# keyboardPCB2.net
KiCad netlist of a schematic drawn in EAGLE
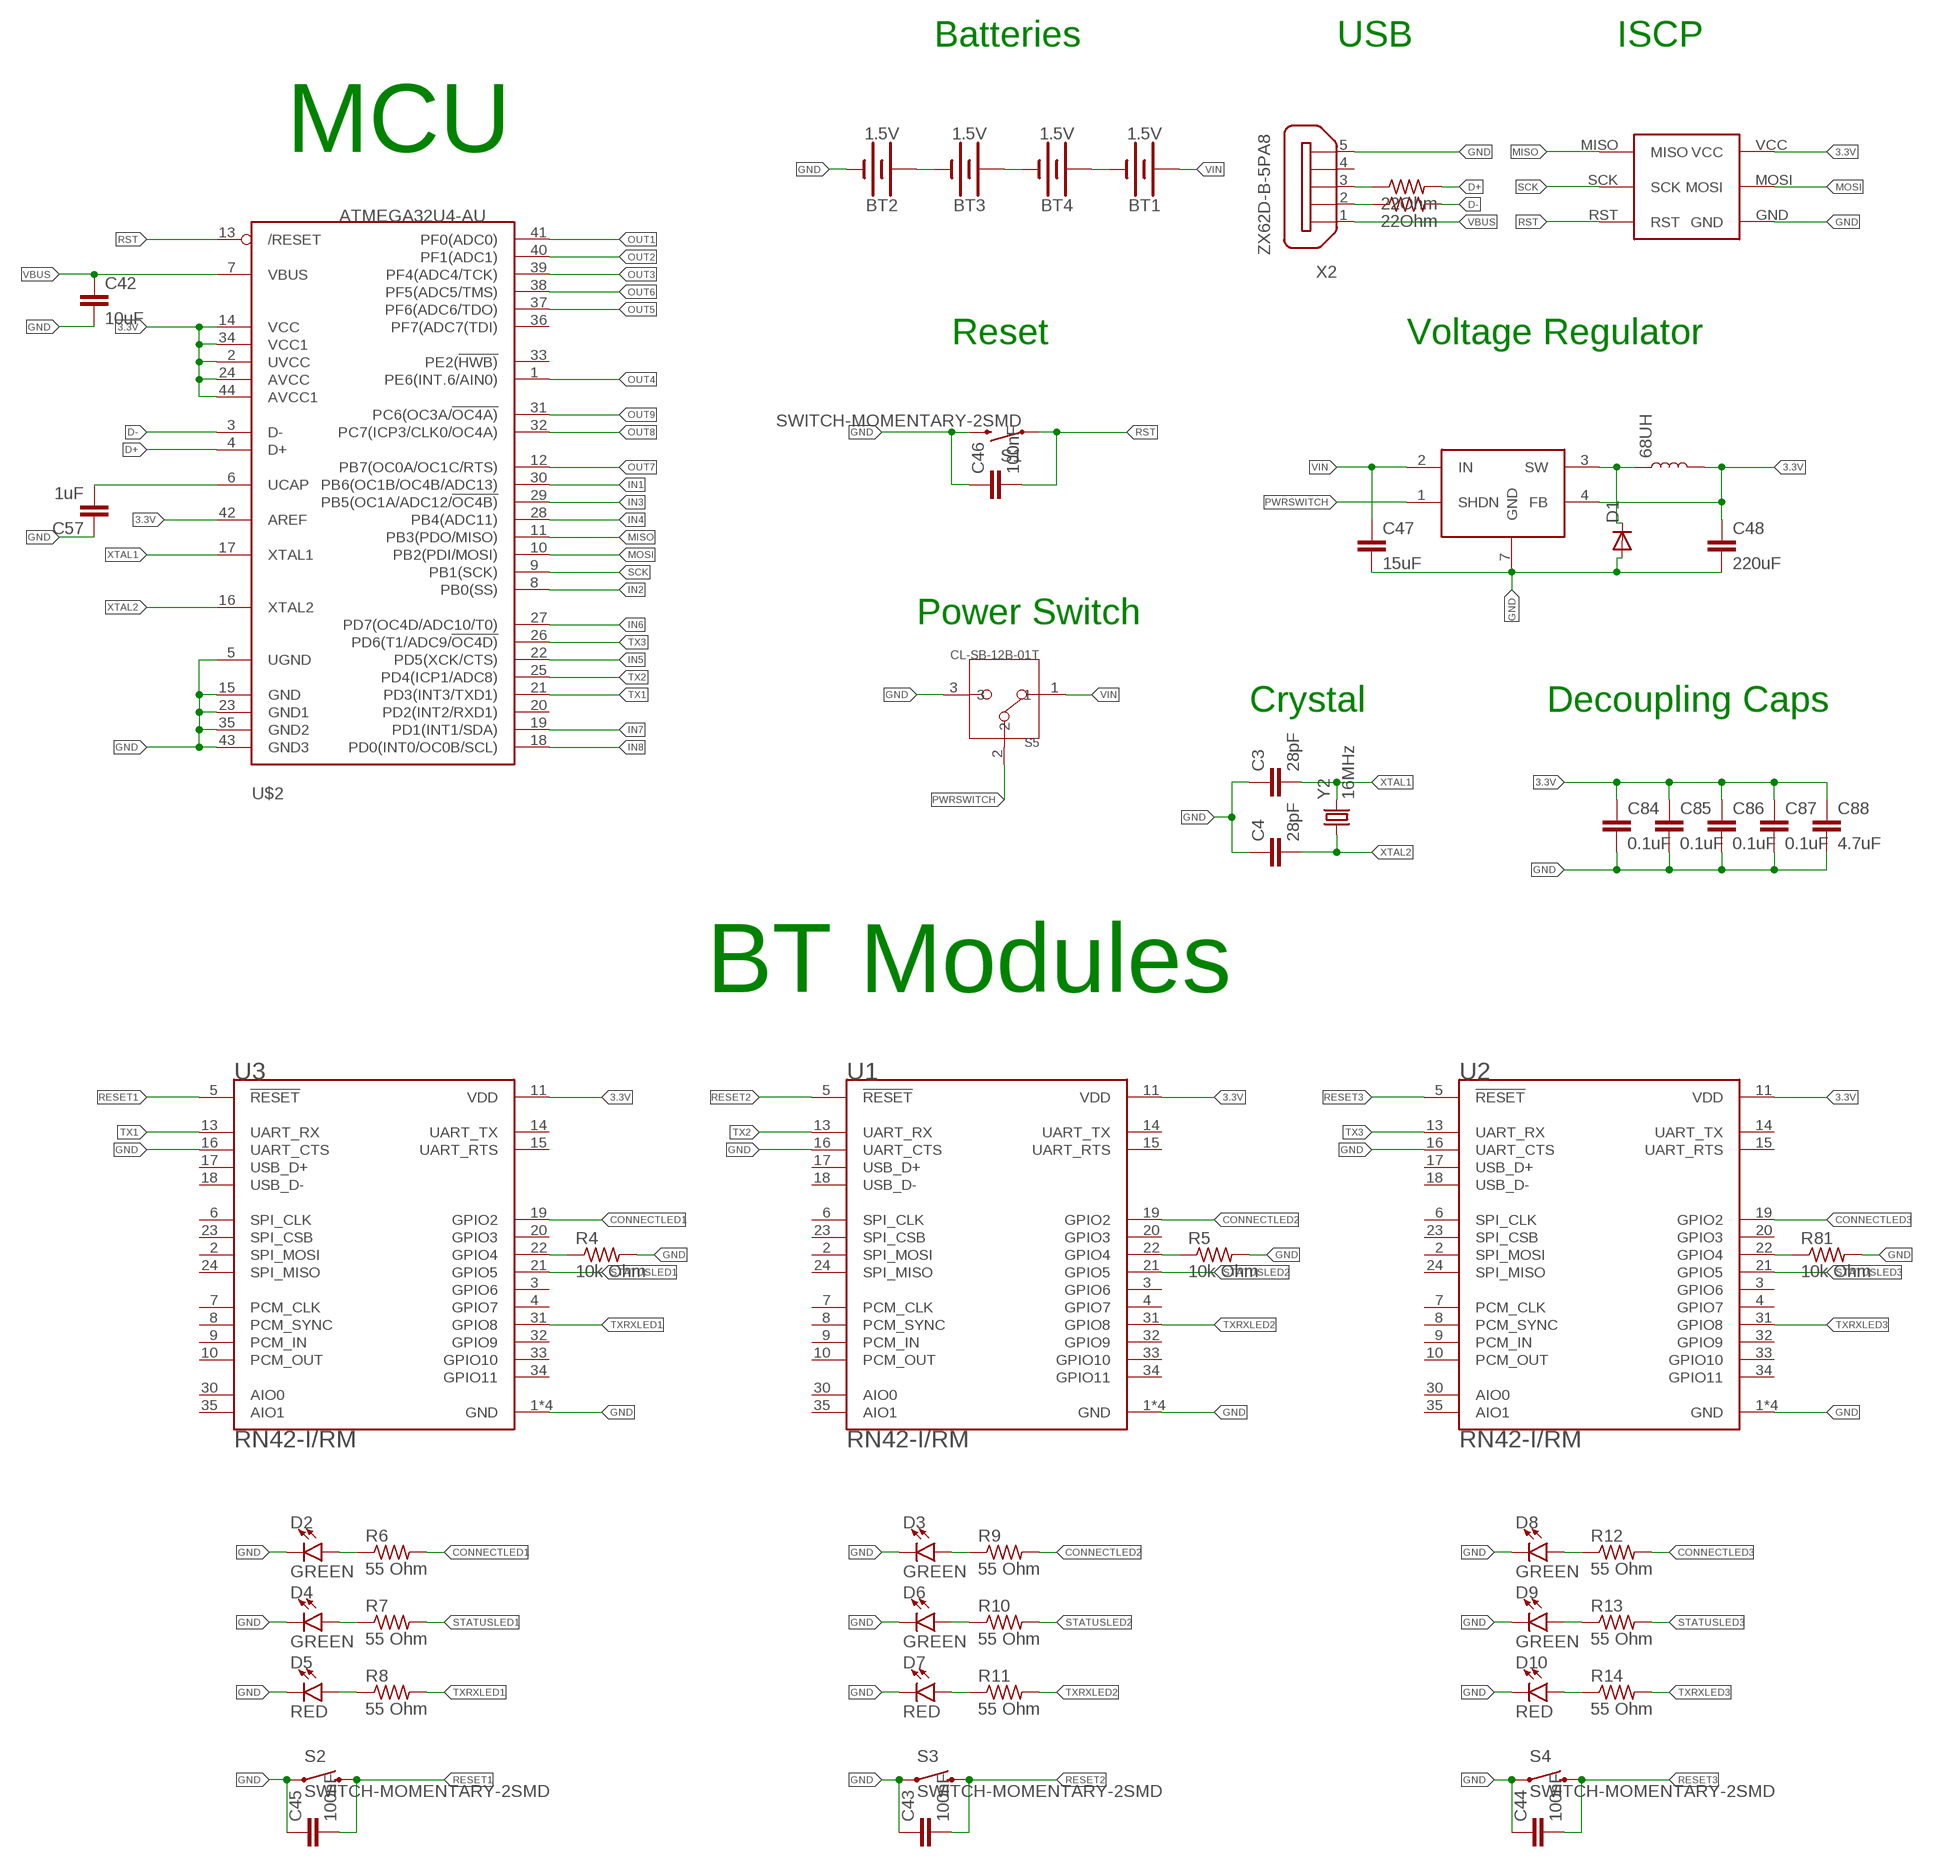
[diagram p0: schematic, sheet 1, part 1 of 2]
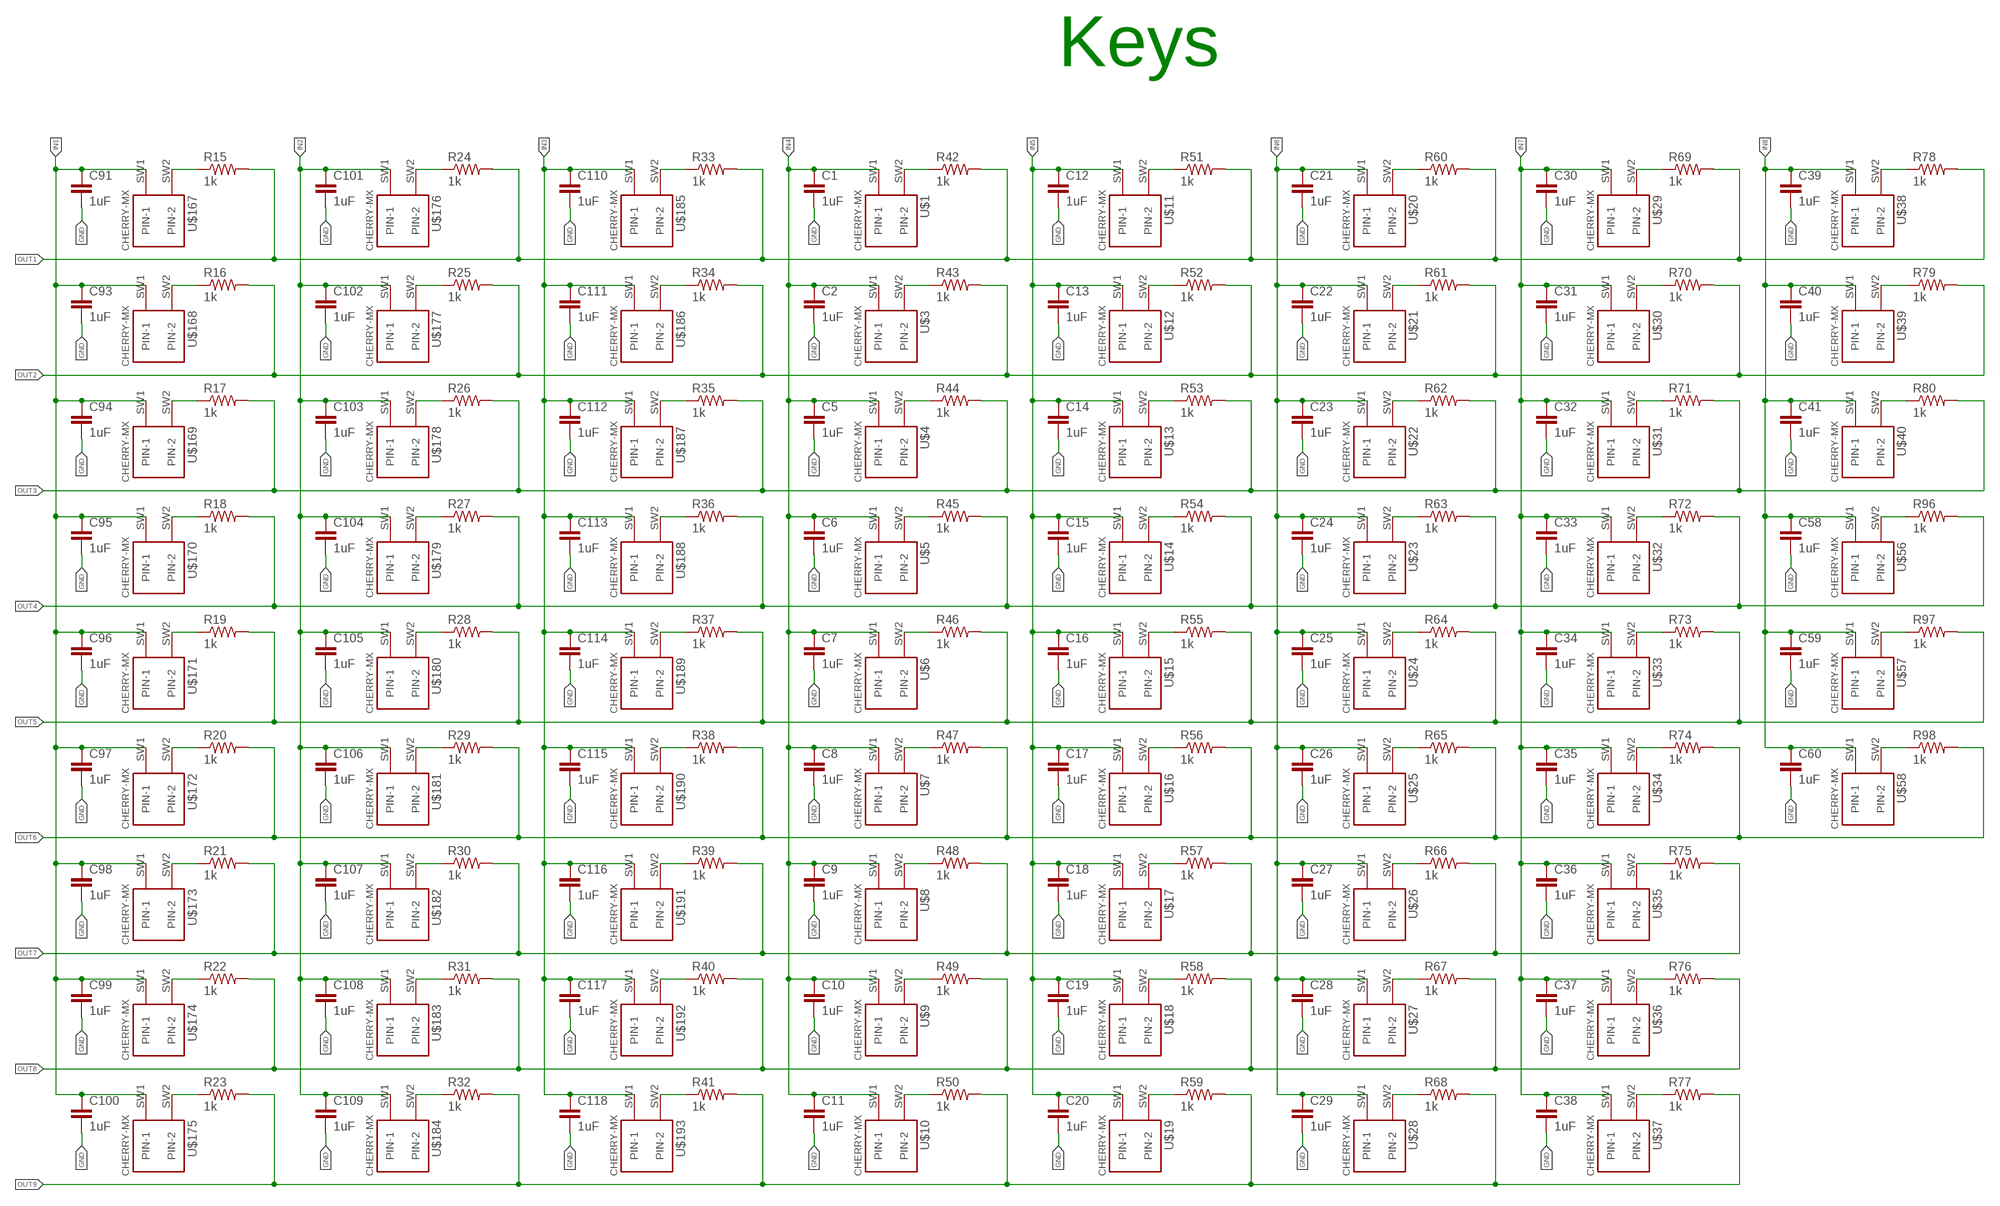
[diagram p1: schematic, sheet 1, part 2 of 2]

(export (version "E")
  (design (tool "Eeschema 10.0.6"))
  (components
    (comp (ref "68UH")
      (value "33nH/±5%/500mA")
      (footprint "eagle-import:0603")
      (libsource (lib "eagle-import") (part "INDUCTOR-0603-33NH"))
    )
    (comp (ref "BT1")
      (value "1.5V")
      (footprint "eagle-import:BATTERY-AA")
      (libsource (lib "eagle-import") (part "BATTERY-AA"))
    )
    (comp (ref "BT2")
      (value "1.5V")
      (footprint "eagle-import:BATTERY-AA")
      (libsource (lib "eagle-import") (part "BATTERY-AA"))
    )
    (comp (ref "BT3")
      (value "1.5V")
      (footprint "eagle-import:BATTERY-AA")
      (libsource (lib "eagle-import") (part "BATTERY-AA"))
    )
    (comp (ref "BT4")
      (value "1.5V")
      (footprint "eagle-import:BATTERY-AA")
      (libsource (lib "eagle-import") (part "BATTERY-AA"))
    )
    (comp (ref "C1")
      (value "1uF")
      (footprint "eagle-import:C0402K")
      (libsource (lib "eagle-import") (part "resistor_348_C-EUC0402K"))
    )
    (comp (ref "C2")
      (value "1uF")
      (footprint "eagle-import:C0402K")
      (libsource (lib "eagle-import") (part "resistor_348_C-EUC0402K"))
    )
    (comp (ref "C3")
      (value "28pF")
      (footprint "eagle-import:C0402K")
      (libsource (lib "eagle-import") (part "resistor_348_C-EUC0402K"))
    )
    (comp (ref "C4")
      (value "28pF")
      (footprint "eagle-import:C0402K")
      (libsource (lib "eagle-import") (part "resistor_348_C-EUC0402K"))
    )
    (comp (ref "C5")
      (value "1uF")
      (footprint "eagle-import:C0402K")
      (libsource (lib "eagle-import") (part "resistor_348_C-EUC0402K"))
    )
    (comp (ref "C6")
      (value "1uF")
      (footprint "eagle-import:C0402K")
      (libsource (lib "eagle-import") (part "resistor_348_C-EUC0402K"))
    )
    (comp (ref "C7")
      (value "1uF")
      (footprint "eagle-import:C0402K")
      (libsource (lib "eagle-import") (part "resistor_348_C-EUC0402K"))
    )
    (comp (ref "C8")
      (value "1uF")
      (footprint "eagle-import:C0402K")
      (libsource (lib "eagle-import") (part "resistor_348_C-EUC0402K"))
    )
    (comp (ref "C9")
      (value "1uF")
      (footprint "eagle-import:C0402K")
      (libsource (lib "eagle-import") (part "resistor_348_C-EUC0402K"))
    )
    (comp (ref "C10")
      (value "1uF")
      (footprint "eagle-import:C0402K")
      (libsource (lib "eagle-import") (part "resistor_348_C-EUC0402K"))
    )
    (comp (ref "C11")
      (value "1uF")
      (footprint "eagle-import:C0402K")
      (libsource (lib "eagle-import") (part "resistor_348_C-EUC0402K"))
    )
    (comp (ref "C12")
      (value "1uF")
      (footprint "eagle-import:C0402K")
      (libsource (lib "eagle-import") (part "resistor_348_C-EUC0402K"))
    )
    (comp (ref "C13")
      (value "1uF")
      (footprint "eagle-import:C0402K")
      (libsource (lib "eagle-import") (part "resistor_348_C-EUC0402K"))
    )
    (comp (ref "C14")
      (value "1uF")
      (footprint "eagle-import:C0402K")
      (libsource (lib "eagle-import") (part "resistor_348_C-EUC0402K"))
    )
    (comp (ref "C15")
      (value "1uF")
      (footprint "eagle-import:C0402K")
      (libsource (lib "eagle-import") (part "resistor_348_C-EUC0402K"))
    )
    (comp (ref "C16")
      (value "1uF")
      (footprint "eagle-import:C0402K")
      (libsource (lib "eagle-import") (part "resistor_348_C-EUC0402K"))
    )
    (comp (ref "C17")
      (value "1uF")
      (footprint "eagle-import:C0402K")
      (libsource (lib "eagle-import") (part "resistor_348_C-EUC0402K"))
    )
    (comp (ref "C18")
      (value "1uF")
      (footprint "eagle-import:C0402K")
      (libsource (lib "eagle-import") (part "resistor_348_C-EUC0402K"))
    )
    (comp (ref "C19")
      (value "1uF")
      (footprint "eagle-import:C0402K")
      (libsource (lib "eagle-import") (part "resistor_348_C-EUC0402K"))
    )
    (comp (ref "C20")
      (value "1uF")
      (footprint "eagle-import:C0402K")
      (libsource (lib "eagle-import") (part "resistor_348_C-EUC0402K"))
    )
    (comp (ref "C21")
      (value "1uF")
      (footprint "eagle-import:C0402K")
      (libsource (lib "eagle-import") (part "resistor_348_C-EUC0402K"))
    )
    (comp (ref "C22")
      (value "1uF")
      (footprint "eagle-import:C0402K")
      (libsource (lib "eagle-import") (part "resistor_348_C-EUC0402K"))
    )
    (comp (ref "C23")
      (value "1uF")
      (footprint "eagle-import:C0402K")
      (libsource (lib "eagle-import") (part "resistor_348_C-EUC0402K"))
    )
    (comp (ref "C24")
      (value "1uF")
      (footprint "eagle-import:C0402K")
      (libsource (lib "eagle-import") (part "resistor_348_C-EUC0402K"))
    )
    (comp (ref "C25")
      (value "1uF")
      (footprint "eagle-import:C0402K")
      (libsource (lib "eagle-import") (part "resistor_348_C-EUC0402K"))
    )
    (comp (ref "C26")
      (value "1uF")
      (footprint "eagle-import:C0402K")
      (libsource (lib "eagle-import") (part "resistor_348_C-EUC0402K"))
    )
    (comp (ref "C27")
      (value "1uF")
      (footprint "eagle-import:C0402K")
      (libsource (lib "eagle-import") (part "resistor_348_C-EUC0402K"))
    )
    (comp (ref "C28")
      (value "1uF")
      (footprint "eagle-import:C0402K")
      (libsource (lib "eagle-import") (part "resistor_348_C-EUC0402K"))
    )
    (comp (ref "C29")
      (value "1uF")
      (footprint "eagle-import:C0402K")
      (libsource (lib "eagle-import") (part "resistor_348_C-EUC0402K"))
    )
    (comp (ref "C30")
      (value "1uF")
      (footprint "eagle-import:C0402K")
      (libsource (lib "eagle-import") (part "resistor_348_C-EUC0402K"))
    )
    (comp (ref "C31")
      (value "1uF")
      (footprint "eagle-import:C0402K")
      (libsource (lib "eagle-import") (part "resistor_348_C-EUC0402K"))
    )
    (comp (ref "C32")
      (value "1uF")
      (footprint "eagle-import:C0402K")
      (libsource (lib "eagle-import") (part "resistor_348_C-EUC0402K"))
    )
    (comp (ref "C33")
      (value "1uF")
      (footprint "eagle-import:C0402K")
      (libsource (lib "eagle-import") (part "resistor_348_C-EUC0402K"))
    )
    (comp (ref "C34")
      (value "1uF")
      (footprint "eagle-import:C0402K")
      (libsource (lib "eagle-import") (part "resistor_348_C-EUC0402K"))
    )
    (comp (ref "C35")
      (value "1uF")
      (footprint "eagle-import:C0402K")
      (libsource (lib "eagle-import") (part "resistor_348_C-EUC0402K"))
    )
    (comp (ref "C36")
      (value "1uF")
      (footprint "eagle-import:C0402K")
      (libsource (lib "eagle-import") (part "resistor_348_C-EUC0402K"))
    )
    (comp (ref "C37")
      (value "1uF")
      (footprint "eagle-import:C0402K")
      (libsource (lib "eagle-import") (part "resistor_348_C-EUC0402K"))
    )
    (comp (ref "C38")
      (value "1uF")
      (footprint "eagle-import:C0402K")
      (libsource (lib "eagle-import") (part "resistor_348_C-EUC0402K"))
    )
    (comp (ref "C39")
      (value "1uF")
      (footprint "eagle-import:C0402K")
      (libsource (lib "eagle-import") (part "resistor_348_C-EUC0402K"))
    )
    (comp (ref "C40")
      (value "1uF")
      (footprint "eagle-import:C0402K")
      (libsource (lib "eagle-import") (part "resistor_348_C-EUC0402K"))
    )
    (comp (ref "C41")
      (value "1uF")
      (footprint "eagle-import:C0402K")
      (libsource (lib "eagle-import") (part "resistor_348_C-EUC0402K"))
    )
    (comp (ref "C42")
      (value "10uF")
      (footprint "eagle-import:C0402K")
      (libsource (lib "eagle-import") (part "resistor_348_C-EUC0402K"))
    )
    (comp (ref "C43")
      (value "100nF")
      (footprint "eagle-import:C0402K")
      (libsource (lib "eagle-import") (part "resistor_348_C-EUC0402K"))
    )
    (comp (ref "C44")
      (value "100nF")
      (footprint "eagle-import:C0402K")
      (libsource (lib "eagle-import") (part "resistor_348_C-EUC0402K"))
    )
    (comp (ref "C45")
      (value "100nF")
      (footprint "eagle-import:C0402K")
      (libsource (lib "eagle-import") (part "resistor_348_C-EUC0402K"))
    )
    (comp (ref "C46")
      (value "100nF")
      (footprint "eagle-import:C0402K")
      (libsource (lib "eagle-import") (part "resistor_348_C-EUC0402K"))
    )
    (comp (ref "C47")
      (value "15uF")
      (footprint "eagle-import:C0603K")
      (libsource (lib "eagle-import") (part "C-EUC0603K"))
    )
    (comp (ref "C48")
      (value "220uF")
      (footprint "eagle-import:C1206")
      (libsource (lib "eagle-import") (part "C-EUC1206"))
    )
    (comp (ref "C57")
      (value "1uF")
      (footprint "eagle-import:C0402K")
      (libsource (lib "eagle-import") (part "resistor_348_C-EUC0402K"))
    )
    (comp (ref "C58")
      (value "1uF")
      (footprint "eagle-import:C0402K")
      (libsource (lib "eagle-import") (part "resistor_348_C-EUC0402K"))
    )
    (comp (ref "C59")
      (value "1uF")
      (footprint "eagle-import:C0402K")
      (libsource (lib "eagle-import") (part "resistor_348_C-EUC0402K"))
    )
    (comp (ref "C60")
      (value "1uF")
      (footprint "eagle-import:C0402K")
      (libsource (lib "eagle-import") (part "resistor_348_C-EUC0402K"))
    )
    (comp (ref "C84")
      (value "0.1uF")
      (footprint "eagle-import:C0402K")
      (libsource (lib "eagle-import") (part "resistor_348_C-EUC0402K"))
    )
    (comp (ref "C85")
      (value "0.1uF")
      (footprint "eagle-import:C0402K")
      (libsource (lib "eagle-import") (part "resistor_348_C-EUC0402K"))
    )
    (comp (ref "C86")
      (value "0.1uF")
      (footprint "eagle-import:C0402K")
      (libsource (lib "eagle-import") (part "resistor_348_C-EUC0402K"))
    )
    (comp (ref "C87")
      (value "0.1uF")
      (footprint "eagle-import:C0402K")
      (libsource (lib "eagle-import") (part "resistor_348_C-EUC0402K"))
    )
    (comp (ref "C88")
      (value "4.7uF")
      (footprint "eagle-import:C0402K")
      (libsource (lib "eagle-import") (part "resistor_348_C-EUC0402K"))
    )
    (comp (ref "C91")
      (value "1uF")
      (footprint "eagle-import:C0402K")
      (libsource (lib "eagle-import") (part "resistor_348_C-EUC0402K"))
    )
    (comp (ref "C93")
      (value "1uF")
      (footprint "eagle-import:C0402K")
      (libsource (lib "eagle-import") (part "resistor_348_C-EUC0402K"))
    )
    (comp (ref "C94")
      (value "1uF")
      (footprint "eagle-import:C0402K")
      (libsource (lib "eagle-import") (part "resistor_348_C-EUC0402K"))
    )
    (comp (ref "C95")
      (value "1uF")
      (footprint "eagle-import:C0402K")
      (libsource (lib "eagle-import") (part "resistor_348_C-EUC0402K"))
    )
    (comp (ref "C96")
      (value "1uF")
      (footprint "eagle-import:C0402K")
      (libsource (lib "eagle-import") (part "resistor_348_C-EUC0402K"))
    )
    (comp (ref "C97")
      (value "1uF")
      (footprint "eagle-import:C0402K")
      (libsource (lib "eagle-import") (part "resistor_348_C-EUC0402K"))
    )
    (comp (ref "C98")
      (value "1uF")
      (footprint "eagle-import:C0402K")
      (libsource (lib "eagle-import") (part "resistor_348_C-EUC0402K"))
    )
    (comp (ref "C99")
      (value "1uF")
      (footprint "eagle-import:C0402K")
      (libsource (lib "eagle-import") (part "resistor_348_C-EUC0402K"))
    )
    (comp (ref "C100")
      (value "1uF")
      (footprint "eagle-import:C0402K")
      (libsource (lib "eagle-import") (part "resistor_348_C-EUC0402K"))
    )
    (comp (ref "C101")
      (value "1uF")
      (footprint "eagle-import:C0402K")
      (libsource (lib "eagle-import") (part "resistor_348_C-EUC0402K"))
    )
    (comp (ref "C102")
      (value "1uF")
      (footprint "eagle-import:C0402K")
      (libsource (lib "eagle-import") (part "resistor_348_C-EUC0402K"))
    )
    (comp (ref "C103")
      (value "1uF")
      (footprint "eagle-import:C0402K")
      (libsource (lib "eagle-import") (part "resistor_348_C-EUC0402K"))
    )
    (comp (ref "C104")
      (value "1uF")
      (footprint "eagle-import:C0402K")
      (libsource (lib "eagle-import") (part "resistor_348_C-EUC0402K"))
    )
    (comp (ref "C105")
      (value "1uF")
      (footprint "eagle-import:C0402K")
      (libsource (lib "eagle-import") (part "resistor_348_C-EUC0402K"))
    )
    (comp (ref "C106")
      (value "1uF")
      (footprint "eagle-import:C0402K")
      (libsource (lib "eagle-import") (part "resistor_348_C-EUC0402K"))
    )
    (comp (ref "C107")
      (value "1uF")
      (footprint "eagle-import:C0402K")
      (libsource (lib "eagle-import") (part "resistor_348_C-EUC0402K"))
    )
    (comp (ref "C108")
      (value "1uF")
      (footprint "eagle-import:C0402K")
      (libsource (lib "eagle-import") (part "resistor_348_C-EUC0402K"))
    )
    (comp (ref "C109")
      (value "1uF")
      (footprint "eagle-import:C0402K")
      (libsource (lib "eagle-import") (part "resistor_348_C-EUC0402K"))
    )
    (comp (ref "C110")
      (value "1uF")
      (footprint "eagle-import:C0402K")
      (libsource (lib "eagle-import") (part "resistor_348_C-EUC0402K"))
    )
    (comp (ref "C111")
      (value "1uF")
      (footprint "eagle-import:C0402K")
      (libsource (lib "eagle-import") (part "resistor_348_C-EUC0402K"))
    )
    (comp (ref "C112")
      (value "1uF")
      (footprint "eagle-import:C0402K")
      (libsource (lib "eagle-import") (part "resistor_348_C-EUC0402K"))
    )
    (comp (ref "C113")
      (value "1uF")
      (footprint "eagle-import:C0402K")
      (libsource (lib "eagle-import") (part "resistor_348_C-EUC0402K"))
    )
    (comp (ref "C114")
      (value "1uF")
      (footprint "eagle-import:C0402K")
      (libsource (lib "eagle-import") (part "resistor_348_C-EUC0402K"))
    )
    (comp (ref "C115")
      (value "1uF")
      (footprint "eagle-import:C0402K")
      (libsource (lib "eagle-import") (part "resistor_348_C-EUC0402K"))
    )
    (comp (ref "C116")
      (value "1uF")
      (footprint "eagle-import:C0402K")
      (libsource (lib "eagle-import") (part "resistor_348_C-EUC0402K"))
    )
    (comp (ref "C117")
      (value "1uF")
      (footprint "eagle-import:C0402K")
      (libsource (lib "eagle-import") (part "resistor_348_C-EUC0402K"))
    )
    (comp (ref "C118")
      (value "1uF")
      (footprint "eagle-import:C0402K")
      (libsource (lib "eagle-import") (part "resistor_348_C-EUC0402K"))
    )
    (comp (ref "D1")
      (value "S2A")
      (footprint "eagle-import:DO214AA")
      (fields (field (name "MF") "Fairchild"))
      (libsource (lib "eagle-import") (part "S2A"))
    )
    (comp (ref "D2")
      (value "GREEN")
      (footprint "eagle-import:LED-0603")
      (libsource (lib "eagle-import") (part "LED-GREEN0603"))
    )
    (comp (ref "D3")
      (value "GREEN")
      (footprint "eagle-import:LED-0603")
      (libsource (lib "eagle-import") (part "LED-GREEN0603"))
    )
    (comp (ref "D4")
      (value "GREEN")
      (footprint "eagle-import:LED-0603")
      (libsource (lib "eagle-import") (part "LED-GREEN0603"))
    )
    (comp (ref "D5")
      (value "RED")
      (footprint "eagle-import:LED-0603")
      (libsource (lib "eagle-import") (part "LED-RED0603"))
    )
    (comp (ref "D6")
      (value "GREEN")
      (footprint "eagle-import:LED-0603")
      (libsource (lib "eagle-import") (part "LED-GREEN0603"))
    )
    (comp (ref "D7")
      (value "RED")
      (footprint "eagle-import:LED-0603")
      (libsource (lib "eagle-import") (part "LED-RED0603"))
    )
    (comp (ref "D8")
      (value "GREEN")
      (footprint "eagle-import:LED-0603")
      (libsource (lib "eagle-import") (part "LED-GREEN0603"))
    )
    (comp (ref "D9")
      (value "GREEN")
      (footprint "eagle-import:LED-0603")
      (libsource (lib "eagle-import") (part "LED-GREEN0603"))
    )
    (comp (ref "D10")
      (value "RED")
      (footprint "eagle-import:LED-0603")
      (libsource (lib "eagle-import") (part "LED-RED0603"))
    )
    (comp (ref "R2")
      (value "22Ohm")
      (footprint "eagle-import:R0402")
      (libsource (lib "eagle-import") (part "R-US_R0402"))
    )
    (comp (ref "R3")
      (value "22Ohm")
      (footprint "eagle-import:R0402")
      (libsource (lib "eagle-import") (part "R-US_R0402"))
    )
    (comp (ref "R4")
      (value "10k Ohm")
      (footprint "eagle-import:R0402")
      (libsource (lib "eagle-import") (part "R-US_R0402"))
    )
    (comp (ref "R5")
      (value "10k Ohm")
      (footprint "eagle-import:R0402")
      (libsource (lib "eagle-import") (part "R-US_R0402"))
    )
    (comp (ref "R6")
      (value "55 Ohm")
      (footprint "eagle-import:R0402")
      (libsource (lib "eagle-import") (part "R-US_R0402"))
    )
    (comp (ref "R7")
      (value "55 Ohm")
      (footprint "eagle-import:R0402")
      (libsource (lib "eagle-import") (part "R-US_R0402"))
    )
    (comp (ref "R8")
      (value "55 Ohm")
      (footprint "eagle-import:R0402")
      (libsource (lib "eagle-import") (part "R-US_R0402"))
    )
    (comp (ref "R9")
      (value "55 Ohm")
      (footprint "eagle-import:R0402")
      (libsource (lib "eagle-import") (part "R-US_R0402"))
    )
    (comp (ref "R10")
      (value "55 Ohm")
      (footprint "eagle-import:R0402")
      (libsource (lib "eagle-import") (part "R-US_R0402"))
    )
    (comp (ref "R11")
      (value "55 Ohm")
      (footprint "eagle-import:R0402")
      (libsource (lib "eagle-import") (part "R-US_R0402"))
    )
    (comp (ref "R12")
      (value "55 Ohm")
      (footprint "eagle-import:R0402")
      (libsource (lib "eagle-import") (part "R-US_R0402"))
    )
    (comp (ref "R13")
      (value "55 Ohm")
      (footprint "eagle-import:R0402")
      (libsource (lib "eagle-import") (part "R-US_R0402"))
    )
    (comp (ref "R14")
      (value "55 Ohm")
      (footprint "eagle-import:R0402")
      (libsource (lib "eagle-import") (part "R-US_R0402"))
    )
    (comp (ref "R15")
      (value "1k")
      (footprint "eagle-import:R0402")
      (libsource (lib "eagle-import") (part "R-US_R0402"))
    )
    (comp (ref "R16")
      (value "1k")
      (footprint "eagle-import:R0402")
      (libsource (lib "eagle-import") (part "R-US_R0402"))
    )
    (comp (ref "R17")
      (value "1k")
      (footprint "eagle-import:R0402")
      (libsource (lib "eagle-import") (part "R-US_R0402"))
    )
    (comp (ref "R18")
      (value "1k")
      (footprint "eagle-import:R0402")
      (libsource (lib "eagle-import") (part "R-US_R0402"))
    )
    (comp (ref "R19")
      (value "1k")
      (footprint "eagle-import:R0402")
      (libsource (lib "eagle-import") (part "R-US_R0402"))
    )
    (comp (ref "R20")
      (value "1k")
      (footprint "eagle-import:R0402")
      (libsource (lib "eagle-import") (part "R-US_R0402"))
    )
    (comp (ref "R21")
      (value "1k")
      (footprint "eagle-import:R0402")
      (libsource (lib "eagle-import") (part "R-US_R0402"))
    )
    (comp (ref "R22")
      (value "1k")
      (footprint "eagle-import:R0402")
      (libsource (lib "eagle-import") (part "R-US_R0402"))
    )
    (comp (ref "R23")
      (value "1k")
      (footprint "eagle-import:R0402")
      (libsource (lib "eagle-import") (part "R-US_R0402"))
    )
    (comp (ref "R24")
      (value "1k")
      (footprint "eagle-import:R0402")
      (libsource (lib "eagle-import") (part "R-US_R0402"))
    )
    (comp (ref "R25")
      (value "1k")
      (footprint "eagle-import:R0402")
      (libsource (lib "eagle-import") (part "R-US_R0402"))
    )
    (comp (ref "R26")
      (value "1k")
      (footprint "eagle-import:R0402")
      (libsource (lib "eagle-import") (part "R-US_R0402"))
    )
    (comp (ref "R27")
      (value "1k")
      (footprint "eagle-import:R0402")
      (libsource (lib "eagle-import") (part "R-US_R0402"))
    )
    (comp (ref "R28")
      (value "1k")
      (footprint "eagle-import:R0402")
      (libsource (lib "eagle-import") (part "R-US_R0402"))
    )
    (comp (ref "R29")
      (value "1k")
      (footprint "eagle-import:R0402")
      (libsource (lib "eagle-import") (part "R-US_R0402"))
    )
    (comp (ref "R30")
      (value "1k")
      (footprint "eagle-import:R0402")
      (libsource (lib "eagle-import") (part "R-US_R0402"))
    )
    (comp (ref "R31")
      (value "1k")
      (footprint "eagle-import:R0402")
      (libsource (lib "eagle-import") (part "R-US_R0402"))
    )
    (comp (ref "R32")
      (value "1k")
      (footprint "eagle-import:R0402")
      (libsource (lib "eagle-import") (part "R-US_R0402"))
    )
    (comp (ref "R33")
      (value "1k")
      (footprint "eagle-import:R0402")
      (libsource (lib "eagle-import") (part "R-US_R0402"))
    )
    (comp (ref "R34")
      (value "1k")
      (footprint "eagle-import:R0402")
      (libsource (lib "eagle-import") (part "R-US_R0402"))
    )
    (comp (ref "R35")
      (value "1k")
      (footprint "eagle-import:R0402")
      (libsource (lib "eagle-import") (part "R-US_R0402"))
    )
    (comp (ref "R36")
      (value "1k")
      (footprint "eagle-import:R0402")
      (libsource (lib "eagle-import") (part "R-US_R0402"))
    )
    (comp (ref "R37")
      (value "1k")
      (footprint "eagle-import:R0402")
      (libsource (lib "eagle-import") (part "R-US_R0402"))
    )
    (comp (ref "R38")
      (value "1k")
      (footprint "eagle-import:R0402")
      (libsource (lib "eagle-import") (part "R-US_R0402"))
    )
    (comp (ref "R39")
      (value "1k")
      (footprint "eagle-import:R0402")
      (libsource (lib "eagle-import") (part "R-US_R0402"))
    )
    (comp (ref "R40")
      (value "1k")
      (footprint "eagle-import:R0402")
      (libsource (lib "eagle-import") (part "R-US_R0402"))
    )
    (comp (ref "R41")
      (value "1k")
      (footprint "eagle-import:R0402")
      (libsource (lib "eagle-import") (part "R-US_R0402"))
    )
    (comp (ref "R42")
      (value "1k")
      (footprint "eagle-import:R0402")
      (libsource (lib "eagle-import") (part "R-US_R0402"))
    )
    (comp (ref "R43")
      (value "1k")
      (footprint "eagle-import:R0402")
      (libsource (lib "eagle-import") (part "R-US_R0402"))
    )
    (comp (ref "R44")
      (value "1k")
      (footprint "eagle-import:R0402")
      (libsource (lib "eagle-import") (part "R-US_R0402"))
    )
    (comp (ref "R45")
      (value "1k")
      (footprint "eagle-import:R0402")
      (libsource (lib "eagle-import") (part "R-US_R0402"))
    )
    (comp (ref "R46")
      (value "1k")
      (footprint "eagle-import:R0402")
      (libsource (lib "eagle-import") (part "R-US_R0402"))
    )
    (comp (ref "R47")
      (value "1k")
      (footprint "eagle-import:R0402")
      (libsource (lib "eagle-import") (part "R-US_R0402"))
    )
    (comp (ref "R48")
      (value "1k")
      (footprint "eagle-import:R0402")
      (libsource (lib "eagle-import") (part "R-US_R0402"))
    )
    (comp (ref "R49")
      (value "1k")
      (footprint "eagle-import:R0402")
      (libsource (lib "eagle-import") (part "R-US_R0402"))
    )
    (comp (ref "R50")
      (value "1k")
      (footprint "eagle-import:R0402")
      (libsource (lib "eagle-import") (part "R-US_R0402"))
    )
    (comp (ref "R51")
      (value "1k")
      (footprint "eagle-import:R0402")
      (libsource (lib "eagle-import") (part "R-US_R0402"))
    )
    (comp (ref "R52")
      (value "1k")
      (footprint "eagle-import:R0402")
      (libsource (lib "eagle-import") (part "R-US_R0402"))
    )
    (comp (ref "R53")
      (value "1k")
      (footprint "eagle-import:R0402")
      (libsource (lib "eagle-import") (part "R-US_R0402"))
    )
    (comp (ref "R54")
      (value "1k")
      (footprint "eagle-import:R0402")
      (libsource (lib "eagle-import") (part "R-US_R0402"))
    )
    (comp (ref "R55")
      (value "1k")
      (footprint "eagle-import:R0402")
      (libsource (lib "eagle-import") (part "R-US_R0402"))
    )
    (comp (ref "R56")
      (value "1k")
      (footprint "eagle-import:R0402")
      (libsource (lib "eagle-import") (part "R-US_R0402"))
    )
    (comp (ref "R57")
      (value "1k")
      (footprint "eagle-import:R0402")
      (libsource (lib "eagle-import") (part "R-US_R0402"))
    )
    (comp (ref "R58")
      (value "1k")
      (footprint "eagle-import:R0402")
      (libsource (lib "eagle-import") (part "R-US_R0402"))
    )
    (comp (ref "R59")
      (value "1k")
      (footprint "eagle-import:R0402")
      (libsource (lib "eagle-import") (part "R-US_R0402"))
    )
    (comp (ref "R60")
      (value "1k")
      (footprint "eagle-import:R0402")
      (libsource (lib "eagle-import") (part "R-US_R0402"))
    )
    (comp (ref "R61")
      (value "1k")
      (footprint "eagle-import:R0402")
      (libsource (lib "eagle-import") (part "R-US_R0402"))
    )
    (comp (ref "R62")
      (value "1k")
      (footprint "eagle-import:R0402")
      (libsource (lib "eagle-import") (part "R-US_R0402"))
    )
    (comp (ref "R63")
      (value "1k")
      (footprint "eagle-import:R0402")
      (libsource (lib "eagle-import") (part "R-US_R0402"))
    )
    (comp (ref "R64")
      (value "1k")
      (footprint "eagle-import:R0402")
      (libsource (lib "eagle-import") (part "R-US_R0402"))
    )
    (comp (ref "R65")
      (value "1k")
      (footprint "eagle-import:R0402")
      (libsource (lib "eagle-import") (part "R-US_R0402"))
    )
    (comp (ref "R66")
      (value "1k")
      (footprint "eagle-import:R0402")
      (libsource (lib "eagle-import") (part "R-US_R0402"))
    )
    (comp (ref "R67")
      (value "1k")
      (footprint "eagle-import:R0402")
      (libsource (lib "eagle-import") (part "R-US_R0402"))
    )
    (comp (ref "R68")
      (value "1k")
      (footprint "eagle-import:R0402")
      (libsource (lib "eagle-import") (part "R-US_R0402"))
    )
    (comp (ref "R69")
      (value "1k")
      (footprint "eagle-import:R0402")
      (libsource (lib "eagle-import") (part "R-US_R0402"))
    )
    (comp (ref "R70")
      (value "1k")
      (footprint "eagle-import:R0402")
      (libsource (lib "eagle-import") (part "R-US_R0402"))
    )
    (comp (ref "R71")
      (value "1k")
      (footprint "eagle-import:R0402")
      (libsource (lib "eagle-import") (part "R-US_R0402"))
    )
    (comp (ref "R72")
      (value "1k")
      (footprint "eagle-import:R0402")
      (libsource (lib "eagle-import") (part "R-US_R0402"))
    )
    (comp (ref "R73")
      (value "1k")
      (footprint "eagle-import:R0402")
      (libsource (lib "eagle-import") (part "R-US_R0402"))
    )
    (comp (ref "R74")
      (value "1k")
      (footprint "eagle-import:R0402")
      (libsource (lib "eagle-import") (part "R-US_R0402"))
    )
    (comp (ref "R75")
      (value "1k")
      (footprint "eagle-import:R0402")
      (libsource (lib "eagle-import") (part "R-US_R0402"))
    )
    (comp (ref "R76")
      (value "1k")
      (footprint "eagle-import:R0402")
      (libsource (lib "eagle-import") (part "R-US_R0402"))
    )
    (comp (ref "R77")
      (value "1k")
      (footprint "eagle-import:R0402")
      (libsource (lib "eagle-import") (part "R-US_R0402"))
    )
    (comp (ref "R78")
      (value "1k")
      (footprint "eagle-import:R0402")
      (libsource (lib "eagle-import") (part "R-US_R0402"))
    )
    (comp (ref "R79")
      (value "1k")
      (footprint "eagle-import:R0402")
      (libsource (lib "eagle-import") (part "R-US_R0402"))
    )
    (comp (ref "R80")
      (value "1k")
      (footprint "eagle-import:R0402")
      (libsource (lib "eagle-import") (part "R-US_R0402"))
    )
    (comp (ref "R81")
      (value "10k Ohm")
      (footprint "eagle-import:R0402")
      (libsource (lib "eagle-import") (part "R-US_R0402"))
    )
    (comp (ref "R96")
      (value "1k")
      (footprint "eagle-import:R0402")
      (libsource (lib "eagle-import") (part "R-US_R0402"))
    )
    (comp (ref "R97")
      (value "1k")
      (footprint "eagle-import:R0402")
      (libsource (lib "eagle-import") (part "R-US_R0402"))
    )
    (comp (ref "R98")
      (value "1k")
      (footprint "eagle-import:R0402")
      (libsource (lib "eagle-import") (part "R-US_R0402"))
    )
    (comp (ref "S1")
      (value "SWITCH-MOMENTARY-2SMD")
      (footprint "eagle-import:TACTILE-SWITCH-SMD")
      (libsource (lib "eagle-import") (part "SWITCH-MOMENTARY-2SMD"))
    )
    (comp (ref "S2")
      (value "SWITCH-MOMENTARY-2SMD")
      (footprint "eagle-import:TACTILE-SWITCH-SMD")
      (libsource (lib "eagle-import") (part "SWITCH-MOMENTARY-2SMD"))
    )
    (comp (ref "S3")
      (value "SWITCH-MOMENTARY-2SMD")
      (footprint "eagle-import:TACTILE-SWITCH-SMD")
      (libsource (lib "eagle-import") (part "SWITCH-MOMENTARY-2SMD"))
    )
    (comp (ref "S4")
      (value "SWITCH-MOMENTARY-2SMD")
      (footprint "eagle-import:TACTILE-SWITCH-SMD")
      (libsource (lib "eagle-import") (part "SWITCH-MOMENTARY-2SMD"))
    )
    (comp (ref "S5")
      (value "CL-SB-12B-01T")
      (footprint "eagle-import:CL-SB-12B")
      (fields (field (name "MF") "Nidec Copal"))
      (libsource (lib "eagle-import") (part "CL-SB-12B-01T"))
    )
    (comp (ref "U$1")
      (value "CHERRY-MX")
      (footprint "eagle-import:CHERRY-MX")
      (libsource (lib "eagle-import") (part "CHERRY-MX"))
    )
    (comp (ref "U$2")
      (value "ATMEGA32U4-AU")
      (footprint "eagle-import:TQFP44")
      (libsource (lib "eagle-import") (part "ATMEGA32U4-AU"))
    )
    (comp (ref "U$3")
      (value "CHERRY-MX")
      (footprint "eagle-import:CHERRY-MX")
      (libsource (lib "eagle-import") (part "CHERRY-MX"))
    )
    (comp (ref "U$4")
      (value "CHERRY-MX")
      (footprint "eagle-import:CHERRY-MX")
      (libsource (lib "eagle-import") (part "CHERRY-MX"))
    )
    (comp (ref "U$5")
      (value "CHERRY-MX")
      (footprint "eagle-import:CHERRY-MX")
      (libsource (lib "eagle-import") (part "CHERRY-MX"))
    )
    (comp (ref "U$6")
      (value "CHERRY-MX")
      (footprint "eagle-import:CHERRY-MX")
      (libsource (lib "eagle-import") (part "CHERRY-MX"))
    )
    (comp (ref "U$7")
      (value "CHERRY-MX")
      (footprint "eagle-import:CHERRY-MX")
      (libsource (lib "eagle-import") (part "CHERRY-MX"))
    )
    (comp (ref "U$8")
      (value "CHERRY-MX")
      (footprint "eagle-import:CHERRY-MX")
      (libsource (lib "eagle-import") (part "CHERRY-MX"))
    )
    (comp (ref "U$9")
      (value "CHERRY-MX")
      (footprint "eagle-import:CHERRY-MX")
      (libsource (lib "eagle-import") (part "CHERRY-MX"))
    )
    (comp (ref "U$10")
      (value "CHERRY-MX")
      (footprint "eagle-import:CHERRY-MX")
      (libsource (lib "eagle-import") (part "CHERRY-MX"))
    )
    (comp (ref "U$11")
      (value "CHERRY-MX")
      (footprint "eagle-import:CHERRY-MX")
      (libsource (lib "eagle-import") (part "CHERRY-MX"))
    )
    (comp (ref "U$12")
      (value "CHERRY-MX")
      (footprint "eagle-import:CHERRY-MX")
      (libsource (lib "eagle-import") (part "CHERRY-MX"))
    )
    (comp (ref "U$13")
      (value "CHERRY-MX")
      (footprint "eagle-import:CHERRY-MX")
      (libsource (lib "eagle-import") (part "CHERRY-MX"))
    )
    (comp (ref "U$14")
      (value "CHERRY-MX")
      (footprint "eagle-import:CHERRY-MX")
      (libsource (lib "eagle-import") (part "CHERRY-MX"))
    )
    (comp (ref "U$15")
      (value "CHERRY-MX")
      (footprint "eagle-import:CHERRY-MX")
      (libsource (lib "eagle-import") (part "CHERRY-MX"))
    )
    (comp (ref "U$16")
      (value "CHERRY-MX")
      (footprint "eagle-import:CHERRY-MX")
      (libsource (lib "eagle-import") (part "CHERRY-MX"))
    )
    (comp (ref "U$17")
      (value "CHERRY-MX")
      (footprint "eagle-import:CHERRY-MX")
      (libsource (lib "eagle-import") (part "CHERRY-MX"))
    )
    (comp (ref "U$18")
      (value "CHERRY-MX")
      (footprint "eagle-import:CHERRY-MX")
      (libsource (lib "eagle-import") (part "CHERRY-MX"))
    )
    (comp (ref "U$19")
      (value "CHERRY-MX")
      (footprint "eagle-import:CHERRY-MX")
      (libsource (lib "eagle-import") (part "CHERRY-MX"))
    )
    (comp (ref "U$20")
      (value "CHERRY-MX")
      (footprint "eagle-import:CHERRY-MX")
      (libsource (lib "eagle-import") (part "CHERRY-MX"))
    )
    (comp (ref "U$21")
      (value "CHERRY-MX")
      (footprint "eagle-import:CHERRY-MX")
      (libsource (lib "eagle-import") (part "CHERRY-MX"))
    )
    (comp (ref "U$22")
      (value "CHERRY-MX")
      (footprint "eagle-import:CHERRY-MX")
      (libsource (lib "eagle-import") (part "CHERRY-MX"))
    )
    (comp (ref "U$23")
      (value "CHERRY-MX")
      (footprint "eagle-import:CHERRY-MX")
      (libsource (lib "eagle-import") (part "CHERRY-MX"))
    )
    (comp (ref "U$24")
      (value "CHERRY-MX")
      (footprint "eagle-import:CHERRY-MX")
      (libsource (lib "eagle-import") (part "CHERRY-MX"))
    )
    (comp (ref "U$25")
      (value "CHERRY-MX")
      (footprint "eagle-import:CHERRY-MX")
      (libsource (lib "eagle-import") (part "CHERRY-MX"))
    )
    (comp (ref "U$26")
      (value "CHERRY-MX")
      (footprint "eagle-import:CHERRY-MX")
      (libsource (lib "eagle-import") (part "CHERRY-MX"))
    )
    (comp (ref "U$27")
      (value "CHERRY-MX")
      (footprint "eagle-import:CHERRY-MX")
      (libsource (lib "eagle-import") (part "CHERRY-MX"))
    )
    (comp (ref "U$28")
      (value "CHERRY-MX")
      (footprint "eagle-import:CHERRY-MX")
      (libsource (lib "eagle-import") (part "CHERRY-MX"))
    )
    (comp (ref "U$29")
      (value "CHERRY-MX")
      (footprint "eagle-import:CHERRY-MX")
      (libsource (lib "eagle-import") (part "CHERRY-MX"))
    )
    (comp (ref "U$30")
      (value "CHERRY-MX")
      (footprint "eagle-import:CHERRY-MX")
      (libsource (lib "eagle-import") (part "CHERRY-MX"))
    )
    (comp (ref "U$31")
      (value "CHERRY-MX")
      (footprint "eagle-import:CHERRY-MX")
      (libsource (lib "eagle-import") (part "CHERRY-MX"))
    )
    (comp (ref "U$32")
      (value "CHERRY-MX")
      (footprint "eagle-import:CHERRY-MX")
      (libsource (lib "eagle-import") (part "CHERRY-MX"))
    )
    (comp (ref "U$33")
      (value "CHERRY-MX")
      (footprint "eagle-import:CHERRY-MX")
      (libsource (lib "eagle-import") (part "CHERRY-MX"))
    )
    (comp (ref "U$34")
      (value "CHERRY-MX")
      (footprint "eagle-import:CHERRY-MX")
      (libsource (lib "eagle-import") (part "CHERRY-MX"))
    )
    (comp (ref "U$35")
      (value "CHERRY-MX")
      (footprint "eagle-import:CHERRY-MX")
      (libsource (lib "eagle-import") (part "CHERRY-MX"))
    )
    (comp (ref "U$36")
      (value "CHERRY-MX")
      (footprint "eagle-import:CHERRY-MX")
      (libsource (lib "eagle-import") (part "CHERRY-MX"))
    )
    (comp (ref "U$37")
      (value "CHERRY-MX")
      (footprint "eagle-import:CHERRY-MX")
      (libsource (lib "eagle-import") (part "CHERRY-MX"))
    )
    (comp (ref "U$38")
      (value "CHERRY-MX")
      (footprint "eagle-import:CHERRY-MX")
      (libsource (lib "eagle-import") (part "CHERRY-MX"))
    )
    (comp (ref "U$39")
      (value "CHERRY-MX")
      (footprint "eagle-import:CHERRY-MX")
      (libsource (lib "eagle-import") (part "CHERRY-MX"))
    )
    (comp (ref "U$40")
      (value "CHERRY-MX")
      (footprint "eagle-import:CHERRY-MX")
      (libsource (lib "eagle-import") (part "CHERRY-MX"))
    )
    (comp (ref "U$56")
      (value "CHERRY-MX")
      (footprint "eagle-import:CHERRY-MX")
      (libsource (lib "eagle-import") (part "CHERRY-MX"))
    )
    (comp (ref "U$57")
      (value "CHERRY-MX")
      (footprint "eagle-import:CHERRY-MX")
      (libsource (lib "eagle-import") (part "CHERRY-MX"))
    )
    (comp (ref "U$58")
      (value "CHERRY-MX")
      (footprint "eagle-import:CHERRY-MX")
      (libsource (lib "eagle-import") (part "CHERRY-MX"))
    )
    (comp (ref "U$59")
      (value "AVR-ISP")
      (footprint "eagle-import:AVR-ISP")
      (fields (field (name "MF") "Gravitech"))
      (libsource (lib "eagle-import") (part "AVR-ISP"))
    )
    (comp (ref "U$166")
      (value "MIC4680")
      (footprint "eagle-import:SOIC-8")
      (fields (field (name "MF") "Micrel"))
      (libsource (lib "eagle-import") (part "MIC4680"))
    )
    (comp (ref "U$167")
      (value "CHERRY-MX")
      (footprint "eagle-import:CHERRY-MX")
      (libsource (lib "eagle-import") (part "CHERRY-MX"))
    )
    (comp (ref "U$168")
      (value "CHERRY-MX")
      (footprint "eagle-import:CHERRY-MX")
      (libsource (lib "eagle-import") (part "CHERRY-MX"))
    )
    (comp (ref "U$169")
      (value "CHERRY-MX")
      (footprint "eagle-import:CHERRY-MX")
      (libsource (lib "eagle-import") (part "CHERRY-MX"))
    )
    (comp (ref "U$170")
      (value "CHERRY-MX")
      (footprint "eagle-import:CHERRY-MX")
      (libsource (lib "eagle-import") (part "CHERRY-MX"))
    )
    (comp (ref "U$171")
      (value "CHERRY-MX")
      (footprint "eagle-import:CHERRY-MX")
      (libsource (lib "eagle-import") (part "CHERRY-MX"))
    )
    (comp (ref "U$172")
      (value "CHERRY-MX")
      (footprint "eagle-import:CHERRY-MX")
      (libsource (lib "eagle-import") (part "CHERRY-MX"))
    )
    (comp (ref "U$173")
      (value "CHERRY-MX")
      (footprint "eagle-import:CHERRY-MX")
      (libsource (lib "eagle-import") (part "CHERRY-MX"))
    )
    (comp (ref "U$174")
      (value "CHERRY-MX")
      (footprint "eagle-import:CHERRY-MX")
      (libsource (lib "eagle-import") (part "CHERRY-MX"))
    )
    (comp (ref "U$175")
      (value "CHERRY-MX")
      (footprint "eagle-import:CHERRY-MX")
      (libsource (lib "eagle-import") (part "CHERRY-MX"))
    )
    (comp (ref "U$176")
      (value "CHERRY-MX")
      (footprint "eagle-import:CHERRY-MX")
      (libsource (lib "eagle-import") (part "CHERRY-MX"))
    )
    (comp (ref "U$177")
      (value "CHERRY-MX")
      (footprint "eagle-import:CHERRY-MX")
      (libsource (lib "eagle-import") (part "CHERRY-MX"))
    )
    (comp (ref "U$178")
      (value "CHERRY-MX")
      (footprint "eagle-import:CHERRY-MX")
      (libsource (lib "eagle-import") (part "CHERRY-MX"))
    )
    (comp (ref "U$179")
      (value "CHERRY-MX")
      (footprint "eagle-import:CHERRY-MX")
      (libsource (lib "eagle-import") (part "CHERRY-MX"))
    )
    (comp (ref "U$180")
      (value "CHERRY-MX")
      (footprint "eagle-import:CHERRY-MX")
      (libsource (lib "eagle-import") (part "CHERRY-MX"))
    )
    (comp (ref "U$181")
      (value "CHERRY-MX")
      (footprint "eagle-import:CHERRY-MX")
      (libsource (lib "eagle-import") (part "CHERRY-MX"))
    )
    (comp (ref "U$182")
      (value "CHERRY-MX")
      (footprint "eagle-import:CHERRY-MX")
      (libsource (lib "eagle-import") (part "CHERRY-MX"))
    )
    (comp (ref "U$183")
      (value "CHERRY-MX")
      (footprint "eagle-import:CHERRY-MX")
      (libsource (lib "eagle-import") (part "CHERRY-MX"))
    )
    (comp (ref "U$184")
      (value "CHERRY-MX")
      (footprint "eagle-import:CHERRY-MX")
      (libsource (lib "eagle-import") (part "CHERRY-MX"))
    )
    (comp (ref "U$185")
      (value "CHERRY-MX")
      (footprint "eagle-import:CHERRY-MX")
      (libsource (lib "eagle-import") (part "CHERRY-MX"))
    )
    (comp (ref "U$186")
      (value "CHERRY-MX")
      (footprint "eagle-import:CHERRY-MX")
      (libsource (lib "eagle-import") (part "CHERRY-MX"))
    )
    (comp (ref "U$187")
      (value "CHERRY-MX")
      (footprint "eagle-import:CHERRY-MX")
      (libsource (lib "eagle-import") (part "CHERRY-MX"))
    )
    (comp (ref "U$188")
      (value "CHERRY-MX")
      (footprint "eagle-import:CHERRY-MX")
      (libsource (lib "eagle-import") (part "CHERRY-MX"))
    )
    (comp (ref "U$189")
      (value "CHERRY-MX")
      (footprint "eagle-import:CHERRY-MX")
      (libsource (lib "eagle-import") (part "CHERRY-MX"))
    )
    (comp (ref "U$190")
      (value "CHERRY-MX")
      (footprint "eagle-import:CHERRY-MX")
      (libsource (lib "eagle-import") (part "CHERRY-MX"))
    )
    (comp (ref "U$191")
      (value "CHERRY-MX")
      (footprint "eagle-import:CHERRY-MX")
      (libsource (lib "eagle-import") (part "CHERRY-MX"))
    )
    (comp (ref "U$192")
      (value "CHERRY-MX")
      (footprint "eagle-import:CHERRY-MX")
      (libsource (lib "eagle-import") (part "CHERRY-MX"))
    )
    (comp (ref "U$193")
      (value "CHERRY-MX")
      (footprint "eagle-import:CHERRY-MX")
      (libsource (lib "eagle-import") (part "CHERRY-MX"))
    )
    (comp (ref "U1")
      (value "RN42-I/RM")
      (footprint "eagle-import:XCVR_RN42-I_RM")
      (fields (field (name "MF") "Microchip"))
      (libsource (lib "eagle-import") (part "RN42-I/RM"))
    )
    (comp (ref "U2")
      (value "RN42-I/RM")
      (footprint "eagle-import:XCVR_RN42-I_RM")
      (fields (field (name "MF") "Microchip"))
      (libsource (lib "eagle-import") (part "RN42-I/RM"))
    )
    (comp (ref "U3")
      (value "RN42-I/RM")
      (footprint "eagle-import:XCVR_RN42-I_RM")
      (fields (field (name "MF") "Microchip"))
      (libsource (lib "eagle-import") (part "RN42-I/RM"))
    )
    (comp (ref "X2")
      (value "ZX62D-B-5PA8")
      (footprint "eagle-import:ZX62D-B-5PA8")
      (fields (field (name "MF") "Hirose"))
      (libsource (lib "eagle-import") (part "ZX62D-B-5PA8"))
    )
    (comp (ref "Y2")
      (value "16MHz")
      (footprint "eagle-import:HC49UP")
      (libsource (lib "eagle-import") (part "CRYSTALSMD"))
    )
  )
  (nets
    (net (code "1") (name "3.3V") (class "Default")
      (node (ref "68UH") (pin "2") (pinfunction "2_2") (pintype "passive"))
      (node (ref "C48") (pin "1") (pinfunction "1_1") (pintype "passive"))
      (node (ref "C84") (pin "1") (pinfunction "1_1") (pintype "passive"))
      (node (ref "C85") (pin "1") (pinfunction "1_1") (pintype "passive"))
      (node (ref "C86") (pin "1") (pinfunction "1_1") (pintype "passive"))
      (node (ref "C87") (pin "1") (pinfunction "1_1") (pintype "passive"))
      (node (ref "C88") (pin "1") (pinfunction "1_1") (pintype "passive"))
      (node (ref "U$166") (pin "4") (pinfunction "FB_4") (pintype "bidirectional"))
      (node (ref "U$2") (pin "14") (pinfunction "VCC_14") (pintype "bidirectional"))
      (node (ref "U$2") (pin "2") (pinfunction "UVCC_2") (pintype "bidirectional"))
      (node (ref "U$2") (pin "24") (pinfunction "AVCC_24") (pintype "bidirectional"))
      (node (ref "U$2") (pin "34") (pinfunction "VCC1_34") (pintype "bidirectional"))
      (node (ref "U$2") (pin "42") (pinfunction "AREF_42") (pintype "bidirectional"))
      (node (ref "U$2") (pin "44") (pinfunction "AVCC1_44") (pintype "bidirectional"))
      (node (ref "U$59") (pin "VCC") (pinfunction "VCC_VCC") (pintype "bidirectional"))
      (node (ref "U1") (pin "11") (pinfunction "VDD_11") (pintype "power_in"))
      (node (ref "U2") (pin "11") (pinfunction "VDD_11") (pintype "power_in"))
      (node (ref "U3") (pin "11") (pinfunction "VDD_11") (pintype "power_in"))
    )
    (net (code "2") (name "CONNECTLED1") (class "Default")
      (node (ref "R6") (pin "2") (pinfunction "2_2") (pintype "passive"))
      (node (ref "U3") (pin "19") (pinfunction "GPIO2_19") (pintype "bidirectional"))
    )
    (net (code "3") (name "CONNECTLED2") (class "Default")
      (node (ref "R9") (pin "2") (pinfunction "2_2") (pintype "passive"))
      (node (ref "U1") (pin "19") (pinfunction "GPIO2_19") (pintype "bidirectional"))
    )
    (net (code "4") (name "CONNECTLED3") (class "Default")
      (node (ref "R12") (pin "2") (pinfunction "2_2") (pintype "passive"))
      (node (ref "U2") (pin "19") (pinfunction "GPIO2_19") (pintype "bidirectional"))
    )
    (net (code "5") (name "D+") (class "Default")
      (node (ref "R2") (pin "2") (pinfunction "2_2") (pintype "passive"))
      (node (ref "U$2") (pin "4") (pinfunction "D+_4") (pintype "bidirectional"))
    )
    (net (code "6") (name "D-") (class "Default")
      (node (ref "R3") (pin "2") (pinfunction "2_2") (pintype "passive"))
      (node (ref "U$2") (pin "3") (pinfunction "D-_3") (pintype "bidirectional"))
    )
    (net (code "7") (name "GND") (class "Default")
      (node (ref "BT2") (pin "GND@1") (pinfunction "-_GND@1") (pintype "power_in"))
      (node (ref "C1") (pin "2") (pinfunction "2_2") (pintype "passive"))
      (node (ref "C10") (pin "2") (pinfunction "2_2") (pintype "passive"))
      (node (ref "C100") (pin "2") (pinfunction "2_2") (pintype "passive"))
      (node (ref "C101") (pin "2") (pinfunction "2_2") (pintype "passive"))
      (node (ref "C102") (pin "2") (pinfunction "2_2") (pintype "passive"))
      (node (ref "C103") (pin "2") (pinfunction "2_2") (pintype "passive"))
      (node (ref "C104") (pin "2") (pinfunction "2_2") (pintype "passive"))
      (node (ref "C105") (pin "2") (pinfunction "2_2") (pintype "passive"))
      (node (ref "C106") (pin "2") (pinfunction "2_2") (pintype "passive"))
      (node (ref "C107") (pin "2") (pinfunction "2_2") (pintype "passive"))
      (node (ref "C108") (pin "2") (pinfunction "2_2") (pintype "passive"))
      (node (ref "C109") (pin "2") (pinfunction "2_2") (pintype "passive"))
      (node (ref "C11") (pin "2") (pinfunction "2_2") (pintype "passive"))
      (node (ref "C110") (pin "2") (pinfunction "2_2") (pintype "passive"))
      (node (ref "C111") (pin "2") (pinfunction "2_2") (pintype "passive"))
      (node (ref "C112") (pin "2") (pinfunction "2_2") (pintype "passive"))
      (node (ref "C113") (pin "2") (pinfunction "2_2") (pintype "passive"))
      (node (ref "C114") (pin "2") (pinfunction "2_2") (pintype "passive"))
      (node (ref "C115") (pin "2") (pinfunction "2_2") (pintype "passive"))
      (node (ref "C116") (pin "2") (pinfunction "2_2") (pintype "passive"))
      (node (ref "C117") (pin "2") (pinfunction "2_2") (pintype "passive"))
      (node (ref "C118") (pin "2") (pinfunction "2_2") (pintype "passive"))
      (node (ref "C12") (pin "2") (pinfunction "2_2") (pintype "passive"))
      (node (ref "C13") (pin "2") (pinfunction "2_2") (pintype "passive"))
      (node (ref "C14") (pin "2") (pinfunction "2_2") (pintype "passive"))
      (node (ref "C15") (pin "2") (pinfunction "2_2") (pintype "passive"))
      (node (ref "C16") (pin "2") (pinfunction "2_2") (pintype "passive"))
      (node (ref "C17") (pin "2") (pinfunction "2_2") (pintype "passive"))
      (node (ref "C18") (pin "2") (pinfunction "2_2") (pintype "passive"))
      (node (ref "C19") (pin "2") (pinfunction "2_2") (pintype "passive"))
      (node (ref "C2") (pin "2") (pinfunction "2_2") (pintype "passive"))
      (node (ref "C20") (pin "2") (pinfunction "2_2") (pintype "passive"))
      (node (ref "C21") (pin "2") (pinfunction "2_2") (pintype "passive"))
      (node (ref "C22") (pin "2") (pinfunction "2_2") (pintype "passive"))
      (node (ref "C23") (pin "2") (pinfunction "2_2") (pintype "passive"))
      (node (ref "C24") (pin "2") (pinfunction "2_2") (pintype "passive"))
      (node (ref "C25") (pin "2") (pinfunction "2_2") (pintype "passive"))
      (node (ref "C26") (pin "2") (pinfunction "2_2") (pintype "passive"))
      (node (ref "C27") (pin "2") (pinfunction "2_2") (pintype "passive"))
      (node (ref "C28") (pin "2") (pinfunction "2_2") (pintype "passive"))
      (node (ref "C29") (pin "2") (pinfunction "2_2") (pintype "passive"))
      (node (ref "C3") (pin "1") (pinfunction "1_1") (pintype "passive"))
      (node (ref "C30") (pin "2") (pinfunction "2_2") (pintype "passive"))
      (node (ref "C31") (pin "2") (pinfunction "2_2") (pintype "passive"))
      (node (ref "C32") (pin "2") (pinfunction "2_2") (pintype "passive"))
      (node (ref "C33") (pin "2") (pinfunction "2_2") (pintype "passive"))
      (node (ref "C34") (pin "2") (pinfunction "2_2") (pintype "passive"))
      (node (ref "C35") (pin "2") (pinfunction "2_2") (pintype "passive"))
      (node (ref "C36") (pin "2") (pinfunction "2_2") (pintype "passive"))
      (node (ref "C37") (pin "2") (pinfunction "2_2") (pintype "passive"))
      (node (ref "C38") (pin "2") (pinfunction "2_2") (pintype "passive"))
      (node (ref "C39") (pin "2") (pinfunction "2_2") (pintype "passive"))
      (node (ref "C4") (pin "1") (pinfunction "1_1") (pintype "passive"))
      (node (ref "C40") (pin "2") (pinfunction "2_2") (pintype "passive"))
      (node (ref "C41") (pin "2") (pinfunction "2_2") (pintype "passive"))
      (node (ref "C42") (pin "2") (pinfunction "2_2") (pintype "passive"))
      (node (ref "C43") (pin "1") (pinfunction "1_1") (pintype "passive"))
      (node (ref "C44") (pin "1") (pinfunction "1_1") (pintype "passive"))
      (node (ref "C45") (pin "1") (pinfunction "1_1") (pintype "passive"))
      (node (ref "C46") (pin "1") (pinfunction "1_1") (pintype "passive"))
      (node (ref "C47") (pin "2") (pinfunction "2_2") (pintype "passive"))
      (node (ref "C48") (pin "2") (pinfunction "2_2") (pintype "passive"))
      (node (ref "C5") (pin "2") (pinfunction "2_2") (pintype "passive"))
      (node (ref "C57") (pin "1") (pinfunction "1_1") (pintype "passive"))
      (node (ref "C58") (pin "2") (pinfunction "2_2") (pintype "passive"))
      (node (ref "C59") (pin "2") (pinfunction "2_2") (pintype "passive"))
      (node (ref "C6") (pin "2") (pinfunction "2_2") (pintype "passive"))
      (node (ref "C60") (pin "2") (pinfunction "2_2") (pintype "passive"))
      (node (ref "C7") (pin "2") (pinfunction "2_2") (pintype "passive"))
      (node (ref "C8") (pin "2") (pinfunction "2_2") (pintype "passive"))
      (node (ref "C84") (pin "2") (pinfunction "2_2") (pintype "passive"))
      (node (ref "C85") (pin "2") (pinfunction "2_2") (pintype "passive"))
      (node (ref "C86") (pin "2") (pinfunction "2_2") (pintype "passive"))
      (node (ref "C87") (pin "2") (pinfunction "2_2") (pintype "passive"))
      (node (ref "C88") (pin "2") (pinfunction "2_2") (pintype "passive"))
      (node (ref "C9") (pin "2") (pinfunction "2_2") (pintype "passive"))
      (node (ref "C91") (pin "2") (pinfunction "2_2") (pintype "passive"))
      (node (ref "C93") (pin "2") (pinfunction "2_2") (pintype "passive"))
      (node (ref "C94") (pin "2") (pinfunction "2_2") (pintype "passive"))
      (node (ref "C95") (pin "2") (pinfunction "2_2") (pintype "passive"))
      (node (ref "C96") (pin "2") (pinfunction "2_2") (pintype "passive"))
      (node (ref "C97") (pin "2") (pinfunction "2_2") (pintype "passive"))
      (node (ref "C98") (pin "2") (pinfunction "2_2") (pintype "passive"))
      (node (ref "C99") (pin "2") (pinfunction "2_2") (pintype "passive"))
      (node (ref "D1") (pin "A") (pinfunction "A_A") (pintype "passive"))
      (node (ref "D10") (pin "C") (pinfunction "C_C") (pintype "passive"))
      (node (ref "D2") (pin "C") (pinfunction "C_C") (pintype "passive"))
      (node (ref "D3") (pin "C") (pinfunction "C_C") (pintype "passive"))
      (node (ref "D4") (pin "C") (pinfunction "C_C") (pintype "passive"))
      (node (ref "D5") (pin "C") (pinfunction "C_C") (pintype "passive"))
      (node (ref "D6") (pin "C") (pinfunction "C_C") (pintype "passive"))
      (node (ref "D7") (pin "C") (pinfunction "C_C") (pintype "passive"))
      (node (ref "D8") (pin "C") (pinfunction "C_C") (pintype "passive"))
      (node (ref "D9") (pin "C") (pinfunction "C_C") (pintype "passive"))
      (node (ref "R4") (pin "2") (pinfunction "2_2") (pintype "passive"))
      (node (ref "R5") (pin "2") (pinfunction "2_2") (pintype "passive"))
      (node (ref "R81") (pin "2") (pinfunction "2_2") (pintype "passive"))
      (node (ref "S1") (pin "3") (pinfunction "2_3") (pintype "passive"))
      (node (ref "S2") (pin "1") (pinfunction "1_1") (pintype "passive"))
      (node (ref "S3") (pin "1") (pinfunction "1_1") (pintype "passive"))
      (node (ref "S4") (pin "1") (pinfunction "1_1") (pintype "passive"))
      (node (ref "S5") (pin "3") (pinfunction "3_3") (pintype "bidirectional"))
      (node (ref "U$166") (pin "5") (pinfunction "GND_5") (pintype "power_in"))
      (node (ref "U$166") (pin "6") (pinfunction "GND_6") (pintype "power_in"))
      (node (ref "U$166") (pin "7") (pinfunction "GND_7") (pintype "power_in"))
      (node (ref "U$166") (pin "8") (pinfunction "GND_8") (pintype "power_in"))
      (node (ref "U$2") (pin "15") (pinfunction "GND_15") (pintype "bidirectional"))
      (node (ref "U$2") (pin "23") (pinfunction "GND1_23") (pintype "bidirectional"))
      (node (ref "U$2") (pin "35") (pinfunction "GND2_35") (pintype "bidirectional"))
      (node (ref "U$2") (pin "43") (pinfunction "GND3_43") (pintype "bidirectional"))
      (node (ref "U$2") (pin "5") (pinfunction "UGND_5") (pintype "bidirectional"))
      (node (ref "U$59") (pin "GND") (pinfunction "GND_GND") (pintype "bidirectional"))
      (node (ref "U1") (pin "1") (pinfunction "GND_1") (pintype "power_in"))
      (node (ref "U1") (pin "12") (pinfunction "GND_12") (pintype "power_in"))
      (node (ref "U1") (pin "16") (pinfunction "UART_CTS_16") (pintype "input"))
      (node (ref "U1") (pin "28") (pinfunction "GND_28") (pintype "power_in"))
      (node (ref "U1") (pin "29") (pinfunction "GND_29") (pintype "power_in"))
      (node (ref "U2") (pin "1") (pinfunction "GND_1") (pintype "power_in"))
      (node (ref "U2") (pin "12") (pinfunction "GND_12") (pintype "power_in"))
      (node (ref "U2") (pin "16") (pinfunction "UART_CTS_16") (pintype "input"))
      (node (ref "U2") (pin "28") (pinfunction "GND_28") (pintype "power_in"))
      (node (ref "U2") (pin "29") (pinfunction "GND_29") (pintype "power_in"))
      (node (ref "U3") (pin "1") (pinfunction "GND_1") (pintype "power_in"))
      (node (ref "U3") (pin "12") (pinfunction "GND_12") (pintype "power_in"))
      (node (ref "U3") (pin "16") (pinfunction "UART_CTS_16") (pintype "input"))
      (node (ref "U3") (pin "28") (pinfunction "GND_28") (pintype "power_in"))
      (node (ref "U3") (pin "29") (pinfunction "GND_29") (pintype "power_in"))
      (node (ref "X2") (pin "5") (pinfunction "5_5") (pintype "passive"))
    )
    (net (code "8") (name "IN1") (class "Default")
      (node (ref "C100") (pin "1") (pinfunction "1_1") (pintype "passive"))
      (node (ref "C91") (pin "1") (pinfunction "1_1") (pintype "passive"))
      (node (ref "C93") (pin "1") (pinfunction "1_1") (pintype "passive"))
      (node (ref "C94") (pin "1") (pinfunction "1_1") (pintype "passive"))
      (node (ref "C95") (pin "1") (pinfunction "1_1") (pintype "passive"))
      (node (ref "C96") (pin "1") (pinfunction "1_1") (pintype "passive"))
      (node (ref "C97") (pin "1") (pinfunction "1_1") (pintype "passive"))
      (node (ref "C98") (pin "1") (pinfunction "1_1") (pintype "passive"))
      (node (ref "C99") (pin "1") (pinfunction "1_1") (pintype "passive"))
      (node (ref "U$167") (pin "SW1") (pinfunction "PIN-1_SW1") (pintype "bidirectional"))
      (node (ref "U$168") (pin "SW1") (pinfunction "PIN-1_SW1") (pintype "bidirectional"))
      (node (ref "U$169") (pin "SW1") (pinfunction "PIN-1_SW1") (pintype "bidirectional"))
      (node (ref "U$170") (pin "SW1") (pinfunction "PIN-1_SW1") (pintype "bidirectional"))
      (node (ref "U$171") (pin "SW1") (pinfunction "PIN-1_SW1") (pintype "bidirectional"))
      (node (ref "U$172") (pin "SW1") (pinfunction "PIN-1_SW1") (pintype "bidirectional"))
      (node (ref "U$173") (pin "SW1") (pinfunction "PIN-1_SW1") (pintype "bidirectional"))
      (node (ref "U$174") (pin "SW1") (pinfunction "PIN-1_SW1") (pintype "bidirectional"))
      (node (ref "U$175") (pin "SW1") (pinfunction "PIN-1_SW1") (pintype "bidirectional"))
      (node (ref "U$2") (pin "30") (pinfunction "PB6(OC1B/OC4B/ADC13)_30") (pintype "bidirectional"))
    )
    (net (code "9") (name "IN2") (class "Default")
      (node (ref "C101") (pin "1") (pinfunction "1_1") (pintype "passive"))
      (node (ref "C102") (pin "1") (pinfunction "1_1") (pintype "passive"))
      (node (ref "C103") (pin "1") (pinfunction "1_1") (pintype "passive"))
      (node (ref "C104") (pin "1") (pinfunction "1_1") (pintype "passive"))
      (node (ref "C105") (pin "1") (pinfunction "1_1") (pintype "passive"))
      (node (ref "C106") (pin "1") (pinfunction "1_1") (pintype "passive"))
      (node (ref "C107") (pin "1") (pinfunction "1_1") (pintype "passive"))
      (node (ref "C108") (pin "1") (pinfunction "1_1") (pintype "passive"))
      (node (ref "C109") (pin "1") (pinfunction "1_1") (pintype "passive"))
      (node (ref "U$176") (pin "SW1") (pinfunction "PIN-1_SW1") (pintype "bidirectional"))
      (node (ref "U$177") (pin "SW1") (pinfunction "PIN-1_SW1") (pintype "bidirectional"))
      (node (ref "U$178") (pin "SW1") (pinfunction "PIN-1_SW1") (pintype "bidirectional"))
      (node (ref "U$179") (pin "SW1") (pinfunction "PIN-1_SW1") (pintype "bidirectional"))
      (node (ref "U$180") (pin "SW1") (pinfunction "PIN-1_SW1") (pintype "bidirectional"))
      (node (ref "U$181") (pin "SW1") (pinfunction "PIN-1_SW1") (pintype "bidirectional"))
      (node (ref "U$182") (pin "SW1") (pinfunction "PIN-1_SW1") (pintype "bidirectional"))
      (node (ref "U$183") (pin "SW1") (pinfunction "PIN-1_SW1") (pintype "bidirectional"))
      (node (ref "U$184") (pin "SW1") (pinfunction "PIN-1_SW1") (pintype "bidirectional"))
      (node (ref "U$2") (pin "8") (pinfunction "PB0(SS)_8") (pintype "bidirectional"))
    )
    (net (code "10") (name "IN3") (class "Default")
      (node (ref "C110") (pin "1") (pinfunction "1_1") (pintype "passive"))
      (node (ref "C111") (pin "1") (pinfunction "1_1") (pintype "passive"))
      (node (ref "C112") (pin "1") (pinfunction "1_1") (pintype "passive"))
      (node (ref "C113") (pin "1") (pinfunction "1_1") (pintype "passive"))
      (node (ref "C114") (pin "1") (pinfunction "1_1") (pintype "passive"))
      (node (ref "C115") (pin "1") (pinfunction "1_1") (pintype "passive"))
      (node (ref "C116") (pin "1") (pinfunction "1_1") (pintype "passive"))
      (node (ref "C117") (pin "1") (pinfunction "1_1") (pintype "passive"))
      (node (ref "C118") (pin "1") (pinfunction "1_1") (pintype "passive"))
      (node (ref "U$185") (pin "SW1") (pinfunction "PIN-1_SW1") (pintype "bidirectional"))
      (node (ref "U$186") (pin "SW1") (pinfunction "PIN-1_SW1") (pintype "bidirectional"))
      (node (ref "U$187") (pin "SW1") (pinfunction "PIN-1_SW1") (pintype "bidirectional"))
      (node (ref "U$188") (pin "SW1") (pinfunction "PIN-1_SW1") (pintype "bidirectional"))
      (node (ref "U$189") (pin "SW1") (pinfunction "PIN-1_SW1") (pintype "bidirectional"))
      (node (ref "U$190") (pin "SW1") (pinfunction "PIN-1_SW1") (pintype "bidirectional"))
      (node (ref "U$191") (pin "SW1") (pinfunction "PIN-1_SW1") (pintype "bidirectional"))
      (node (ref "U$192") (pin "SW1") (pinfunction "PIN-1_SW1") (pintype "bidirectional"))
      (node (ref "U$193") (pin "SW1") (pinfunction "PIN-1_SW1") (pintype "bidirectional"))
      (node (ref "U$2") (pin "29") (pinfunction "PB5(OC1A/ADC12/~{OC4B})_29") (pintype "bidirectional"))
    )
    (net (code "11") (name "IN4") (class "Default")
      (node (ref "C1") (pin "1") (pinfunction "1_1") (pintype "passive"))
      (node (ref "C10") (pin "1") (pinfunction "1_1") (pintype "passive"))
      (node (ref "C11") (pin "1") (pinfunction "1_1") (pintype "passive"))
      (node (ref "C2") (pin "1") (pinfunction "1_1") (pintype "passive"))
      (node (ref "C5") (pin "1") (pinfunction "1_1") (pintype "passive"))
      (node (ref "C6") (pin "1") (pinfunction "1_1") (pintype "passive"))
      (node (ref "C7") (pin "1") (pinfunction "1_1") (pintype "passive"))
      (node (ref "C8") (pin "1") (pinfunction "1_1") (pintype "passive"))
      (node (ref "C9") (pin "1") (pinfunction "1_1") (pintype "passive"))
      (node (ref "U$1") (pin "SW1") (pinfunction "PIN-1_SW1") (pintype "bidirectional"))
      (node (ref "U$10") (pin "SW1") (pinfunction "PIN-1_SW1") (pintype "bidirectional"))
      (node (ref "U$2") (pin "28") (pinfunction "PB4(ADC11)_28") (pintype "bidirectional"))
      (node (ref "U$3") (pin "SW1") (pinfunction "PIN-1_SW1") (pintype "bidirectional"))
      (node (ref "U$4") (pin "SW1") (pinfunction "PIN-1_SW1") (pintype "bidirectional"))
      (node (ref "U$5") (pin "SW1") (pinfunction "PIN-1_SW1") (pintype "bidirectional"))
      (node (ref "U$6") (pin "SW1") (pinfunction "PIN-1_SW1") (pintype "bidirectional"))
      (node (ref "U$7") (pin "SW1") (pinfunction "PIN-1_SW1") (pintype "bidirectional"))
      (node (ref "U$8") (pin "SW1") (pinfunction "PIN-1_SW1") (pintype "bidirectional"))
      (node (ref "U$9") (pin "SW1") (pinfunction "PIN-1_SW1") (pintype "bidirectional"))
    )
    (net (code "12") (name "IN5") (class "Default")
      (node (ref "C12") (pin "1") (pinfunction "1_1") (pintype "passive"))
      (node (ref "C13") (pin "1") (pinfunction "1_1") (pintype "passive"))
      (node (ref "C14") (pin "1") (pinfunction "1_1") (pintype "passive"))
      (node (ref "C15") (pin "1") (pinfunction "1_1") (pintype "passive"))
      (node (ref "C16") (pin "1") (pinfunction "1_1") (pintype "passive"))
      (node (ref "C17") (pin "1") (pinfunction "1_1") (pintype "passive"))
      (node (ref "C18") (pin "1") (pinfunction "1_1") (pintype "passive"))
      (node (ref "C19") (pin "1") (pinfunction "1_1") (pintype "passive"))
      (node (ref "C20") (pin "1") (pinfunction "1_1") (pintype "passive"))
      (node (ref "U$11") (pin "SW1") (pinfunction "PIN-1_SW1") (pintype "bidirectional"))
      (node (ref "U$12") (pin "SW1") (pinfunction "PIN-1_SW1") (pintype "bidirectional"))
      (node (ref "U$13") (pin "SW1") (pinfunction "PIN-1_SW1") (pintype "bidirectional"))
      (node (ref "U$14") (pin "SW1") (pinfunction "PIN-1_SW1") (pintype "bidirectional"))
      (node (ref "U$15") (pin "SW1") (pinfunction "PIN-1_SW1") (pintype "bidirectional"))
      (node (ref "U$16") (pin "SW1") (pinfunction "PIN-1_SW1") (pintype "bidirectional"))
      (node (ref "U$17") (pin "SW1") (pinfunction "PIN-1_SW1") (pintype "bidirectional"))
      (node (ref "U$18") (pin "SW1") (pinfunction "PIN-1_SW1") (pintype "bidirectional"))
      (node (ref "U$19") (pin "SW1") (pinfunction "PIN-1_SW1") (pintype "bidirectional"))
      (node (ref "U$2") (pin "22") (pinfunction "PD5(XCK/CTS)_22") (pintype "bidirectional"))
    )
    (net (code "13") (name "IN6") (class "Default")
      (node (ref "C21") (pin "1") (pinfunction "1_1") (pintype "passive"))
      (node (ref "C22") (pin "1") (pinfunction "1_1") (pintype "passive"))
      (node (ref "C23") (pin "1") (pinfunction "1_1") (pintype "passive"))
      (node (ref "C24") (pin "1") (pinfunction "1_1") (pintype "passive"))
      (node (ref "C25") (pin "1") (pinfunction "1_1") (pintype "passive"))
      (node (ref "C26") (pin "1") (pinfunction "1_1") (pintype "passive"))
      (node (ref "C27") (pin "1") (pinfunction "1_1") (pintype "passive"))
      (node (ref "C28") (pin "1") (pinfunction "1_1") (pintype "passive"))
      (node (ref "C29") (pin "1") (pinfunction "1_1") (pintype "passive"))
      (node (ref "U$2") (pin "27") (pinfunction "PD7(OC4D/ADC10/T0)_27") (pintype "bidirectional"))
      (node (ref "U$20") (pin "SW1") (pinfunction "PIN-1_SW1") (pintype "bidirectional"))
      (node (ref "U$21") (pin "SW1") (pinfunction "PIN-1_SW1") (pintype "bidirectional"))
      (node (ref "U$22") (pin "SW1") (pinfunction "PIN-1_SW1") (pintype "bidirectional"))
      (node (ref "U$23") (pin "SW1") (pinfunction "PIN-1_SW1") (pintype "bidirectional"))
      (node (ref "U$24") (pin "SW1") (pinfunction "PIN-1_SW1") (pintype "bidirectional"))
      (node (ref "U$25") (pin "SW1") (pinfunction "PIN-1_SW1") (pintype "bidirectional"))
      (node (ref "U$26") (pin "SW1") (pinfunction "PIN-1_SW1") (pintype "bidirectional"))
      (node (ref "U$27") (pin "SW1") (pinfunction "PIN-1_SW1") (pintype "bidirectional"))
      (node (ref "U$28") (pin "SW1") (pinfunction "PIN-1_SW1") (pintype "bidirectional"))
    )
    (net (code "14") (name "IN7") (class "Default")
      (node (ref "C30") (pin "1") (pinfunction "1_1") (pintype "passive"))
      (node (ref "C31") (pin "1") (pinfunction "1_1") (pintype "passive"))
      (node (ref "C32") (pin "1") (pinfunction "1_1") (pintype "passive"))
      (node (ref "C33") (pin "1") (pinfunction "1_1") (pintype "passive"))
      (node (ref "C34") (pin "1") (pinfunction "1_1") (pintype "passive"))
      (node (ref "C35") (pin "1") (pinfunction "1_1") (pintype "passive"))
      (node (ref "C36") (pin "1") (pinfunction "1_1") (pintype "passive"))
      (node (ref "C37") (pin "1") (pinfunction "1_1") (pintype "passive"))
      (node (ref "C38") (pin "1") (pinfunction "1_1") (pintype "passive"))
      (node (ref "U$2") (pin "19") (pinfunction "PD1(INT1/SDA)_19") (pintype "bidirectional"))
      (node (ref "U$29") (pin "SW1") (pinfunction "PIN-1_SW1") (pintype "bidirectional"))
      (node (ref "U$30") (pin "SW1") (pinfunction "PIN-1_SW1") (pintype "bidirectional"))
      (node (ref "U$31") (pin "SW1") (pinfunction "PIN-1_SW1") (pintype "bidirectional"))
      (node (ref "U$32") (pin "SW1") (pinfunction "PIN-1_SW1") (pintype "bidirectional"))
      (node (ref "U$33") (pin "SW1") (pinfunction "PIN-1_SW1") (pintype "bidirectional"))
      (node (ref "U$34") (pin "SW1") (pinfunction "PIN-1_SW1") (pintype "bidirectional"))
      (node (ref "U$35") (pin "SW1") (pinfunction "PIN-1_SW1") (pintype "bidirectional"))
      (node (ref "U$36") (pin "SW1") (pinfunction "PIN-1_SW1") (pintype "bidirectional"))
      (node (ref "U$37") (pin "SW1") (pinfunction "PIN-1_SW1") (pintype "bidirectional"))
    )
    (net (code "15") (name "IN8") (class "Default")
      (node (ref "C39") (pin "1") (pinfunction "1_1") (pintype "passive"))
      (node (ref "C40") (pin "1") (pinfunction "1_1") (pintype "passive"))
      (node (ref "C41") (pin "1") (pinfunction "1_1") (pintype "passive"))
      (node (ref "C58") (pin "1") (pinfunction "1_1") (pintype "passive"))
      (node (ref "C59") (pin "1") (pinfunction "1_1") (pintype "passive"))
      (node (ref "C60") (pin "1") (pinfunction "1_1") (pintype "passive"))
      (node (ref "U$2") (pin "18") (pinfunction "PD0(INT0/OC0B/SCL)_18") (pintype "bidirectional"))
      (node (ref "U$38") (pin "SW1") (pinfunction "PIN-1_SW1") (pintype "bidirectional"))
      (node (ref "U$39") (pin "SW1") (pinfunction "PIN-1_SW1") (pintype "bidirectional"))
      (node (ref "U$40") (pin "SW1") (pinfunction "PIN-1_SW1") (pintype "bidirectional"))
      (node (ref "U$56") (pin "SW1") (pinfunction "PIN-1_SW1") (pintype "bidirectional"))
      (node (ref "U$57") (pin "SW1") (pinfunction "PIN-1_SW1") (pintype "bidirectional"))
      (node (ref "U$58") (pin "SW1") (pinfunction "PIN-1_SW1") (pintype "bidirectional"))
    )
    (net (code "16") (name "MISO") (class "Default")
      (node (ref "U$2") (pin "11") (pinfunction "PB3(PDO/MISO)_11") (pintype "bidirectional"))
      (node (ref "U$59") (pin "MISO") (pinfunction "MISO_MISO") (pintype "bidirectional"))
    )
    (net (code "17") (name "MOSI") (class "Default")
      (node (ref "U$2") (pin "10") (pinfunction "PB2(PDI/MOSI)_10") (pintype "bidirectional"))
      (node (ref "U$59") (pin "MOSI") (pinfunction "MOSI_MOSI") (pintype "bidirectional"))
    )
    (net (code "18") (name "Net-(BT1--)") (class "Default")
      (node (ref "BT1") (pin "GND@1") (pinfunction "-_GND@1") (pintype "power_in"))
      (node (ref "BT4") (pin "PWR@1") (pinfunction "+_PWR@1") (pintype "power_in"))
    )
    (net (code "19") (name "Net-(BT2-+)") (class "Default")
      (node (ref "BT2") (pin "PWR@1") (pinfunction "+_PWR@1") (pintype "power_in"))
      (node (ref "BT3") (pin "GND@1") (pinfunction "-_GND@1") (pintype "power_in"))
    )
    (net (code "20") (name "Net-(BT3-+)") (class "Default")
      (node (ref "BT3") (pin "PWR@1") (pinfunction "+_PWR@1") (pintype "power_in"))
      (node (ref "BT4") (pin "GND@1") (pinfunction "-_GND@1") (pintype "power_in"))
    )
    (net (code "21") (name "Net-(D2-PadA)") (class "Default")
      (node (ref "D2") (pin "A") (pinfunction "A_A") (pintype "passive"))
      (node (ref "R6") (pin "1") (pinfunction "1_1") (pintype "passive"))
    )
    (net (code "22") (name "Net-(D3-PadA)") (class "Default")
      (node (ref "D3") (pin "A") (pinfunction "A_A") (pintype "passive"))
      (node (ref "R9") (pin "1") (pinfunction "1_1") (pintype "passive"))
    )
    (net (code "23") (name "Net-(D4-PadA)") (class "Default")
      (node (ref "D4") (pin "A") (pinfunction "A_A") (pintype "passive"))
      (node (ref "R7") (pin "1") (pinfunction "1_1") (pintype "passive"))
    )
    (net (code "24") (name "Net-(D5-PadA)") (class "Default")
      (node (ref "D5") (pin "A") (pinfunction "A_A") (pintype "passive"))
      (node (ref "R8") (pin "1") (pinfunction "1_1") (pintype "passive"))
    )
    (net (code "25") (name "Net-(D6-PadA)") (class "Default")
      (node (ref "D6") (pin "A") (pinfunction "A_A") (pintype "passive"))
      (node (ref "R10") (pin "1") (pinfunction "1_1") (pintype "passive"))
    )
    (net (code "26") (name "Net-(D7-PadA)") (class "Default")
      (node (ref "D7") (pin "A") (pinfunction "A_A") (pintype "passive"))
      (node (ref "R11") (pin "1") (pinfunction "1_1") (pintype "passive"))
    )
    (net (code "27") (name "Net-(D8-PadA)") (class "Default")
      (node (ref "D8") (pin "A") (pinfunction "A_A") (pintype "passive"))
      (node (ref "R12") (pin "1") (pinfunction "1_1") (pintype "passive"))
    )
    (net (code "28") (name "Net-(D9-PadA)") (class "Default")
      (node (ref "D9") (pin "A") (pinfunction "A_A") (pintype "passive"))
      (node (ref "R13") (pin "1") (pinfunction "1_1") (pintype "passive"))
    )
    (net (code "29") (name "Net-(D10-PadA)") (class "Default")
      (node (ref "D10") (pin "A") (pinfunction "A_A") (pintype "passive"))
      (node (ref "R14") (pin "1") (pinfunction "1_1") (pintype "passive"))
    )
    (net (code "30") (name "Net-(R2-Pad1)") (class "Default")
      (node (ref "R2") (pin "1") (pinfunction "1_1") (pintype "passive"))
      (node (ref "X2") (pin "3") (pinfunction "3_3") (pintype "passive"))
    )
    (net (code "31") (name "Net-(R3-Pad1)") (class "Default")
      (node (ref "R3") (pin "1") (pinfunction "1_1") (pintype "passive"))
      (node (ref "X2") (pin "2") (pinfunction "2_2") (pintype "passive"))
    )
    (net (code "32") (name "Net-(U$1-PIN-2)") (class "Default")
      (node (ref "R42") (pin "1") (pinfunction "1_1") (pintype "passive"))
      (node (ref "U$1") (pin "SW2") (pinfunction "PIN-2_SW2") (pintype "bidirectional"))
    )
    (net (code "33") (name "Net-(U$2-UCAP)") (class "Default")
      (node (ref "C57") (pin "2") (pinfunction "2_2") (pintype "passive"))
      (node (ref "U$2") (pin "6") (pinfunction "UCAP_6") (pintype "bidirectional"))
    )
    (net (code "34") (name "Net-(U$3-PIN-2)") (class "Default")
      (node (ref "R43") (pin "1") (pinfunction "1_1") (pintype "passive"))
      (node (ref "U$3") (pin "SW2") (pinfunction "PIN-2_SW2") (pintype "bidirectional"))
    )
    (net (code "35") (name "Net-(U$4-PIN-2)") (class "Default")
      (node (ref "R44") (pin "1") (pinfunction "1_1") (pintype "passive"))
      (node (ref "U$4") (pin "SW2") (pinfunction "PIN-2_SW2") (pintype "bidirectional"))
    )
    (net (code "36") (name "Net-(U$5-PIN-2)") (class "Default")
      (node (ref "R45") (pin "1") (pinfunction "1_1") (pintype "passive"))
      (node (ref "U$5") (pin "SW2") (pinfunction "PIN-2_SW2") (pintype "bidirectional"))
    )
    (net (code "37") (name "Net-(U$6-PIN-2)") (class "Default")
      (node (ref "R46") (pin "1") (pinfunction "1_1") (pintype "passive"))
      (node (ref "U$6") (pin "SW2") (pinfunction "PIN-2_SW2") (pintype "bidirectional"))
    )
    (net (code "38") (name "Net-(U$7-PIN-2)") (class "Default")
      (node (ref "R47") (pin "1") (pinfunction "1_1") (pintype "passive"))
      (node (ref "U$7") (pin "SW2") (pinfunction "PIN-2_SW2") (pintype "bidirectional"))
    )
    (net (code "39") (name "Net-(U$8-PIN-2)") (class "Default")
      (node (ref "R48") (pin "1") (pinfunction "1_1") (pintype "passive"))
      (node (ref "U$8") (pin "SW2") (pinfunction "PIN-2_SW2") (pintype "bidirectional"))
    )
    (net (code "40") (name "Net-(U$9-PIN-2)") (class "Default")
      (node (ref "R49") (pin "1") (pinfunction "1_1") (pintype "passive"))
      (node (ref "U$9") (pin "SW2") (pinfunction "PIN-2_SW2") (pintype "bidirectional"))
    )
    (net (code "41") (name "Net-(U$10-PIN-2)") (class "Default")
      (node (ref "R50") (pin "1") (pinfunction "1_1") (pintype "passive"))
      (node (ref "U$10") (pin "SW2") (pinfunction "PIN-2_SW2") (pintype "bidirectional"))
    )
    (net (code "42") (name "Net-(U$11-PIN-2)") (class "Default")
      (node (ref "R51") (pin "1") (pinfunction "1_1") (pintype "passive"))
      (node (ref "U$11") (pin "SW2") (pinfunction "PIN-2_SW2") (pintype "bidirectional"))
    )
    (net (code "43") (name "Net-(U$12-PIN-2)") (class "Default")
      (node (ref "R52") (pin "1") (pinfunction "1_1") (pintype "passive"))
      (node (ref "U$12") (pin "SW2") (pinfunction "PIN-2_SW2") (pintype "bidirectional"))
    )
    (net (code "44") (name "Net-(U$13-PIN-2)") (class "Default")
      (node (ref "R53") (pin "1") (pinfunction "1_1") (pintype "passive"))
      (node (ref "U$13") (pin "SW2") (pinfunction "PIN-2_SW2") (pintype "bidirectional"))
    )
    (net (code "45") (name "Net-(U$14-PIN-2)") (class "Default")
      (node (ref "R54") (pin "1") (pinfunction "1_1") (pintype "passive"))
      (node (ref "U$14") (pin "SW2") (pinfunction "PIN-2_SW2") (pintype "bidirectional"))
    )
    (net (code "46") (name "Net-(U$15-PIN-2)") (class "Default")
      (node (ref "R55") (pin "1") (pinfunction "1_1") (pintype "passive"))
      (node (ref "U$15") (pin "SW2") (pinfunction "PIN-2_SW2") (pintype "bidirectional"))
    )
    (net (code "47") (name "Net-(U$16-PIN-2)") (class "Default")
      (node (ref "R56") (pin "1") (pinfunction "1_1") (pintype "passive"))
      (node (ref "U$16") (pin "SW2") (pinfunction "PIN-2_SW2") (pintype "bidirectional"))
    )
    (net (code "48") (name "Net-(U$17-PIN-2)") (class "Default")
      (node (ref "R57") (pin "1") (pinfunction "1_1") (pintype "passive"))
      (node (ref "U$17") (pin "SW2") (pinfunction "PIN-2_SW2") (pintype "bidirectional"))
    )
    (net (code "49") (name "Net-(U$18-PIN-2)") (class "Default")
      (node (ref "R58") (pin "1") (pinfunction "1_1") (pintype "passive"))
      (node (ref "U$18") (pin "SW2") (pinfunction "PIN-2_SW2") (pintype "bidirectional"))
    )
    (net (code "50") (name "Net-(U$19-PIN-2)") (class "Default")
      (node (ref "R59") (pin "1") (pinfunction "1_1") (pintype "passive"))
      (node (ref "U$19") (pin "SW2") (pinfunction "PIN-2_SW2") (pintype "bidirectional"))
    )
    (net (code "51") (name "Net-(U$20-PIN-2)") (class "Default")
      (node (ref "R60") (pin "1") (pinfunction "1_1") (pintype "passive"))
      (node (ref "U$20") (pin "SW2") (pinfunction "PIN-2_SW2") (pintype "bidirectional"))
    )
    (net (code "52") (name "Net-(U$21-PIN-2)") (class "Default")
      (node (ref "R61") (pin "1") (pinfunction "1_1") (pintype "passive"))
      (node (ref "U$21") (pin "SW2") (pinfunction "PIN-2_SW2") (pintype "bidirectional"))
    )
    (net (code "53") (name "Net-(U$22-PIN-2)") (class "Default")
      (node (ref "R62") (pin "1") (pinfunction "1_1") (pintype "passive"))
      (node (ref "U$22") (pin "SW2") (pinfunction "PIN-2_SW2") (pintype "bidirectional"))
    )
    (net (code "54") (name "Net-(U$23-PIN-2)") (class "Default")
      (node (ref "R63") (pin "1") (pinfunction "1_1") (pintype "passive"))
      (node (ref "U$23") (pin "SW2") (pinfunction "PIN-2_SW2") (pintype "bidirectional"))
    )
    (net (code "55") (name "Net-(U$24-PIN-2)") (class "Default")
      (node (ref "R64") (pin "1") (pinfunction "1_1") (pintype "passive"))
      (node (ref "U$24") (pin "SW2") (pinfunction "PIN-2_SW2") (pintype "bidirectional"))
    )
    (net (code "56") (name "Net-(U$25-PIN-2)") (class "Default")
      (node (ref "R65") (pin "1") (pinfunction "1_1") (pintype "passive"))
      (node (ref "U$25") (pin "SW2") (pinfunction "PIN-2_SW2") (pintype "bidirectional"))
    )
    (net (code "57") (name "Net-(U$26-PIN-2)") (class "Default")
      (node (ref "R66") (pin "1") (pinfunction "1_1") (pintype "passive"))
      (node (ref "U$26") (pin "SW2") (pinfunction "PIN-2_SW2") (pintype "bidirectional"))
    )
    (net (code "58") (name "Net-(U$27-PIN-2)") (class "Default")
      (node (ref "R67") (pin "1") (pinfunction "1_1") (pintype "passive"))
      (node (ref "U$27") (pin "SW2") (pinfunction "PIN-2_SW2") (pintype "bidirectional"))
    )
    (net (code "59") (name "Net-(U$28-PIN-2)") (class "Default")
      (node (ref "R68") (pin "1") (pinfunction "1_1") (pintype "passive"))
      (node (ref "U$28") (pin "SW2") (pinfunction "PIN-2_SW2") (pintype "bidirectional"))
    )
    (net (code "60") (name "Net-(U$29-PIN-2)") (class "Default")
      (node (ref "R69") (pin "1") (pinfunction "1_1") (pintype "passive"))
      (node (ref "U$29") (pin "SW2") (pinfunction "PIN-2_SW2") (pintype "bidirectional"))
    )
    (net (code "61") (name "Net-(U$30-PIN-2)") (class "Default")
      (node (ref "R70") (pin "1") (pinfunction "1_1") (pintype "passive"))
      (node (ref "U$30") (pin "SW2") (pinfunction "PIN-2_SW2") (pintype "bidirectional"))
    )
    (net (code "62") (name "Net-(U$31-PIN-2)") (class "Default")
      (node (ref "R71") (pin "1") (pinfunction "1_1") (pintype "passive"))
      (node (ref "U$31") (pin "SW2") (pinfunction "PIN-2_SW2") (pintype "bidirectional"))
    )
    (net (code "63") (name "Net-(U$32-PIN-2)") (class "Default")
      (node (ref "R72") (pin "1") (pinfunction "1_1") (pintype "passive"))
      (node (ref "U$32") (pin "SW2") (pinfunction "PIN-2_SW2") (pintype "bidirectional"))
    )
    (net (code "64") (name "Net-(U$33-PIN-2)") (class "Default")
      (node (ref "R73") (pin "1") (pinfunction "1_1") (pintype "passive"))
      (node (ref "U$33") (pin "SW2") (pinfunction "PIN-2_SW2") (pintype "bidirectional"))
    )
    (net (code "65") (name "Net-(U$34-PIN-2)") (class "Default")
      (node (ref "R74") (pin "1") (pinfunction "1_1") (pintype "passive"))
      (node (ref "U$34") (pin "SW2") (pinfunction "PIN-2_SW2") (pintype "bidirectional"))
    )
    (net (code "66") (name "Net-(U$35-PIN-2)") (class "Default")
      (node (ref "R75") (pin "1") (pinfunction "1_1") (pintype "passive"))
      (node (ref "U$35") (pin "SW2") (pinfunction "PIN-2_SW2") (pintype "bidirectional"))
    )
    (net (code "67") (name "Net-(U$36-PIN-2)") (class "Default")
      (node (ref "R76") (pin "1") (pinfunction "1_1") (pintype "passive"))
      (node (ref "U$36") (pin "SW2") (pinfunction "PIN-2_SW2") (pintype "bidirectional"))
    )
    (net (code "68") (name "Net-(U$37-PIN-2)") (class "Default")
      (node (ref "R77") (pin "1") (pinfunction "1_1") (pintype "passive"))
      (node (ref "U$37") (pin "SW2") (pinfunction "PIN-2_SW2") (pintype "bidirectional"))
    )
    (net (code "69") (name "Net-(U$38-PIN-2)") (class "Default")
      (node (ref "R78") (pin "1") (pinfunction "1_1") (pintype "passive"))
      (node (ref "U$38") (pin "SW2") (pinfunction "PIN-2_SW2") (pintype "bidirectional"))
    )
    (net (code "70") (name "Net-(U$39-PIN-2)") (class "Default")
      (node (ref "R79") (pin "1") (pinfunction "1_1") (pintype "passive"))
      (node (ref "U$39") (pin "SW2") (pinfunction "PIN-2_SW2") (pintype "bidirectional"))
    )
    (net (code "71") (name "Net-(U$40-PIN-2)") (class "Default")
      (node (ref "R80") (pin "1") (pinfunction "1_1") (pintype "passive"))
      (node (ref "U$40") (pin "SW2") (pinfunction "PIN-2_SW2") (pintype "bidirectional"))
    )
    (net (code "72") (name "Net-(U$56-PIN-2)") (class "Default")
      (node (ref "R96") (pin "1") (pinfunction "1_1") (pintype "passive"))
      (node (ref "U$56") (pin "SW2") (pinfunction "PIN-2_SW2") (pintype "bidirectional"))
    )
    (net (code "73") (name "Net-(U$57-PIN-2)") (class "Default")
      (node (ref "R97") (pin "1") (pinfunction "1_1") (pintype "passive"))
      (node (ref "U$57") (pin "SW2") (pinfunction "PIN-2_SW2") (pintype "bidirectional"))
    )
    (net (code "74") (name "Net-(U$58-PIN-2)") (class "Default")
      (node (ref "R98") (pin "1") (pinfunction "1_1") (pintype "passive"))
      (node (ref "U$58") (pin "SW2") (pinfunction "PIN-2_SW2") (pintype "bidirectional"))
    )
    (net (code "75") (name "Net-(U$166-SW)") (class "Default")
      (node (ref "68UH") (pin "1") (pinfunction "1_1") (pintype "passive"))
      (node (ref "D1") (pin "C") (pinfunction "C_C") (pintype "passive"))
      (node (ref "U$166") (pin "3") (pinfunction "SW_3") (pintype "bidirectional"))
    )
    (net (code "76") (name "Net-(U$167-PIN-2)") (class "Default")
      (node (ref "R15") (pin "1") (pinfunction "1_1") (pintype "passive"))
      (node (ref "U$167") (pin "SW2") (pinfunction "PIN-2_SW2") (pintype "bidirectional"))
    )
    (net (code "77") (name "Net-(U$168-PIN-2)") (class "Default")
      (node (ref "R16") (pin "1") (pinfunction "1_1") (pintype "passive"))
      (node (ref "U$168") (pin "SW2") (pinfunction "PIN-2_SW2") (pintype "bidirectional"))
    )
    (net (code "78") (name "Net-(U$169-PIN-2)") (class "Default")
      (node (ref "R17") (pin "1") (pinfunction "1_1") (pintype "passive"))
      (node (ref "U$169") (pin "SW2") (pinfunction "PIN-2_SW2") (pintype "bidirectional"))
    )
    (net (code "79") (name "Net-(U$170-PIN-2)") (class "Default")
      (node (ref "R18") (pin "1") (pinfunction "1_1") (pintype "passive"))
      (node (ref "U$170") (pin "SW2") (pinfunction "PIN-2_SW2") (pintype "bidirectional"))
    )
    (net (code "80") (name "Net-(U$171-PIN-2)") (class "Default")
      (node (ref "R19") (pin "1") (pinfunction "1_1") (pintype "passive"))
      (node (ref "U$171") (pin "SW2") (pinfunction "PIN-2_SW2") (pintype "bidirectional"))
    )
    (net (code "81") (name "Net-(U$172-PIN-2)") (class "Default")
      (node (ref "R20") (pin "1") (pinfunction "1_1") (pintype "passive"))
      (node (ref "U$172") (pin "SW2") (pinfunction "PIN-2_SW2") (pintype "bidirectional"))
    )
    (net (code "82") (name "Net-(U$173-PIN-2)") (class "Default")
      (node (ref "R21") (pin "1") (pinfunction "1_1") (pintype "passive"))
      (node (ref "U$173") (pin "SW2") (pinfunction "PIN-2_SW2") (pintype "bidirectional"))
    )
    (net (code "83") (name "Net-(U$174-PIN-2)") (class "Default")
      (node (ref "R22") (pin "1") (pinfunction "1_1") (pintype "passive"))
      (node (ref "U$174") (pin "SW2") (pinfunction "PIN-2_SW2") (pintype "bidirectional"))
    )
    (net (code "84") (name "Net-(U$175-PIN-2)") (class "Default")
      (node (ref "R23") (pin "1") (pinfunction "1_1") (pintype "passive"))
      (node (ref "U$175") (pin "SW2") (pinfunction "PIN-2_SW2") (pintype "bidirectional"))
    )
    (net (code "85") (name "Net-(U$176-PIN-2)") (class "Default")
      (node (ref "R24") (pin "1") (pinfunction "1_1") (pintype "passive"))
      (node (ref "U$176") (pin "SW2") (pinfunction "PIN-2_SW2") (pintype "bidirectional"))
    )
    (net (code "86") (name "Net-(U$177-PIN-2)") (class "Default")
      (node (ref "R25") (pin "1") (pinfunction "1_1") (pintype "passive"))
      (node (ref "U$177") (pin "SW2") (pinfunction "PIN-2_SW2") (pintype "bidirectional"))
    )
    (net (code "87") (name "Net-(U$178-PIN-2)") (class "Default")
      (node (ref "R26") (pin "1") (pinfunction "1_1") (pintype "passive"))
      (node (ref "U$178") (pin "SW2") (pinfunction "PIN-2_SW2") (pintype "bidirectional"))
    )
    (net (code "88") (name "Net-(U$179-PIN-2)") (class "Default")
      (node (ref "R27") (pin "1") (pinfunction "1_1") (pintype "passive"))
      (node (ref "U$179") (pin "SW2") (pinfunction "PIN-2_SW2") (pintype "bidirectional"))
    )
    (net (code "89") (name "Net-(U$180-PIN-2)") (class "Default")
      (node (ref "R28") (pin "1") (pinfunction "1_1") (pintype "passive"))
      (node (ref "U$180") (pin "SW2") (pinfunction "PIN-2_SW2") (pintype "bidirectional"))
    )
    (net (code "90") (name "Net-(U$181-PIN-2)") (class "Default")
      (node (ref "R29") (pin "1") (pinfunction "1_1") (pintype "passive"))
      (node (ref "U$181") (pin "SW2") (pinfunction "PIN-2_SW2") (pintype "bidirectional"))
    )
    (net (code "91") (name "Net-(U$182-PIN-2)") (class "Default")
      (node (ref "R30") (pin "1") (pinfunction "1_1") (pintype "passive"))
      (node (ref "U$182") (pin "SW2") (pinfunction "PIN-2_SW2") (pintype "bidirectional"))
    )
    (net (code "92") (name "Net-(U$183-PIN-2)") (class "Default")
      (node (ref "R31") (pin "1") (pinfunction "1_1") (pintype "passive"))
      (node (ref "U$183") (pin "SW2") (pinfunction "PIN-2_SW2") (pintype "bidirectional"))
    )
    (net (code "93") (name "Net-(U$184-PIN-2)") (class "Default")
      (node (ref "R32") (pin "1") (pinfunction "1_1") (pintype "passive"))
      (node (ref "U$184") (pin "SW2") (pinfunction "PIN-2_SW2") (pintype "bidirectional"))
    )
    (net (code "94") (name "Net-(U$185-PIN-2)") (class "Default")
      (node (ref "R33") (pin "1") (pinfunction "1_1") (pintype "passive"))
      (node (ref "U$185") (pin "SW2") (pinfunction "PIN-2_SW2") (pintype "bidirectional"))
    )
    (net (code "95") (name "Net-(U$186-PIN-2)") (class "Default")
      (node (ref "R34") (pin "1") (pinfunction "1_1") (pintype "passive"))
      (node (ref "U$186") (pin "SW2") (pinfunction "PIN-2_SW2") (pintype "bidirectional"))
    )
    (net (code "96") (name "Net-(U$187-PIN-2)") (class "Default")
      (node (ref "R35") (pin "1") (pinfunction "1_1") (pintype "passive"))
      (node (ref "U$187") (pin "SW2") (pinfunction "PIN-2_SW2") (pintype "bidirectional"))
    )
    (net (code "97") (name "Net-(U$188-PIN-2)") (class "Default")
      (node (ref "R36") (pin "1") (pinfunction "1_1") (pintype "passive"))
      (node (ref "U$188") (pin "SW2") (pinfunction "PIN-2_SW2") (pintype "bidirectional"))
    )
    (net (code "98") (name "Net-(U$189-PIN-2)") (class "Default")
      (node (ref "R37") (pin "1") (pinfunction "1_1") (pintype "passive"))
      (node (ref "U$189") (pin "SW2") (pinfunction "PIN-2_SW2") (pintype "bidirectional"))
    )
    (net (code "99") (name "Net-(U$190-PIN-2)") (class "Default")
      (node (ref "R38") (pin "1") (pinfunction "1_1") (pintype "passive"))
      (node (ref "U$190") (pin "SW2") (pinfunction "PIN-2_SW2") (pintype "bidirectional"))
    )
    (net (code "100") (name "Net-(U$191-PIN-2)") (class "Default")
      (node (ref "R39") (pin "1") (pinfunction "1_1") (pintype "passive"))
      (node (ref "U$191") (pin "SW2") (pinfunction "PIN-2_SW2") (pintype "bidirectional"))
    )
    (net (code "101") (name "Net-(U$192-PIN-2)") (class "Default")
      (node (ref "R40") (pin "1") (pinfunction "1_1") (pintype "passive"))
      (node (ref "U$192") (pin "SW2") (pinfunction "PIN-2_SW2") (pintype "bidirectional"))
    )
    (net (code "102") (name "Net-(U$193-PIN-2)") (class "Default")
      (node (ref "R41") (pin "1") (pinfunction "1_1") (pintype "passive"))
      (node (ref "U$193") (pin "SW2") (pinfunction "PIN-2_SW2") (pintype "bidirectional"))
    )
    (net (code "103") (name "Net-(U1-GPIO4)") (class "Default")
      (node (ref "R5") (pin "1") (pinfunction "1_1") (pintype "passive"))
      (node (ref "U1") (pin "22") (pinfunction "GPIO4_22") (pintype "bidirectional"))
    )
    (net (code "104") (name "Net-(U2-GPIO4)") (class "Default")
      (node (ref "R81") (pin "1") (pinfunction "1_1") (pintype "passive"))
      (node (ref "U2") (pin "22") (pinfunction "GPIO4_22") (pintype "bidirectional"))
    )
    (net (code "105") (name "Net-(U3-GPIO4)") (class "Default")
      (node (ref "R4") (pin "1") (pinfunction "1_1") (pintype "passive"))
      (node (ref "U3") (pin "22") (pinfunction "GPIO4_22") (pintype "bidirectional"))
    )
    (net (code "106") (name "OUT1") (class "Default")
      (node (ref "R15") (pin "2") (pinfunction "2_2") (pintype "passive"))
      (node (ref "R24") (pin "2") (pinfunction "2_2") (pintype "passive"))
      (node (ref "R33") (pin "2") (pinfunction "2_2") (pintype "passive"))
      (node (ref "R42") (pin "2") (pinfunction "2_2") (pintype "passive"))
      (node (ref "R51") (pin "2") (pinfunction "2_2") (pintype "passive"))
      (node (ref "R60") (pin "2") (pinfunction "2_2") (pintype "passive"))
      (node (ref "R69") (pin "2") (pinfunction "2_2") (pintype "passive"))
      (node (ref "R78") (pin "2") (pinfunction "2_2") (pintype "passive"))
      (node (ref "U$2") (pin "41") (pinfunction "PF0(ADC0)_41") (pintype "bidirectional"))
    )
    (net (code "107") (name "OUT2") (class "Default")
      (node (ref "R16") (pin "2") (pinfunction "2_2") (pintype "passive"))
      (node (ref "R25") (pin "2") (pinfunction "2_2") (pintype "passive"))
      (node (ref "R34") (pin "2") (pinfunction "2_2") (pintype "passive"))
      (node (ref "R43") (pin "2") (pinfunction "2_2") (pintype "passive"))
      (node (ref "R52") (pin "2") (pinfunction "2_2") (pintype "passive"))
      (node (ref "R61") (pin "2") (pinfunction "2_2") (pintype "passive"))
      (node (ref "R70") (pin "2") (pinfunction "2_2") (pintype "passive"))
      (node (ref "R79") (pin "2") (pinfunction "2_2") (pintype "passive"))
      (node (ref "U$2") (pin "40") (pinfunction "PF1(ADC1)_40") (pintype "bidirectional"))
    )
    (net (code "108") (name "OUT3") (class "Default")
      (node (ref "R17") (pin "2") (pinfunction "2_2") (pintype "passive"))
      (node (ref "R26") (pin "2") (pinfunction "2_2") (pintype "passive"))
      (node (ref "R35") (pin "2") (pinfunction "2_2") (pintype "passive"))
      (node (ref "R44") (pin "2") (pinfunction "2_2") (pintype "passive"))
      (node (ref "R53") (pin "2") (pinfunction "2_2") (pintype "passive"))
      (node (ref "R62") (pin "2") (pinfunction "2_2") (pintype "passive"))
      (node (ref "R71") (pin "2") (pinfunction "2_2") (pintype "passive"))
      (node (ref "R80") (pin "2") (pinfunction "2_2") (pintype "passive"))
      (node (ref "U$2") (pin "39") (pinfunction "PF4(ADC4/TCK)_39") (pintype "bidirectional"))
    )
    (net (code "109") (name "OUT4") (class "Default")
      (node (ref "R18") (pin "2") (pinfunction "2_2") (pintype "passive"))
      (node (ref "R27") (pin "2") (pinfunction "2_2") (pintype "passive"))
      (node (ref "R36") (pin "2") (pinfunction "2_2") (pintype "passive"))
      (node (ref "R45") (pin "2") (pinfunction "2_2") (pintype "passive"))
      (node (ref "R54") (pin "2") (pinfunction "2_2") (pintype "passive"))
      (node (ref "R63") (pin "2") (pinfunction "2_2") (pintype "passive"))
      (node (ref "R72") (pin "2") (pinfunction "2_2") (pintype "passive"))
      (node (ref "R96") (pin "2") (pinfunction "2_2") (pintype "passive"))
      (node (ref "U$2") (pin "1") (pinfunction "PE6(INT.6/AIN0)_1") (pintype "bidirectional"))
    )
    (net (code "110") (name "OUT5") (class "Default")
      (node (ref "R19") (pin "2") (pinfunction "2_2") (pintype "passive"))
      (node (ref "R28") (pin "2") (pinfunction "2_2") (pintype "passive"))
      (node (ref "R37") (pin "2") (pinfunction "2_2") (pintype "passive"))
      (node (ref "R46") (pin "2") (pinfunction "2_2") (pintype "passive"))
      (node (ref "R55") (pin "2") (pinfunction "2_2") (pintype "passive"))
      (node (ref "R64") (pin "2") (pinfunction "2_2") (pintype "passive"))
      (node (ref "R73") (pin "2") (pinfunction "2_2") (pintype "passive"))
      (node (ref "R97") (pin "2") (pinfunction "2_2") (pintype "passive"))
      (node (ref "U$2") (pin "37") (pinfunction "PF6(ADC6/TDO)_37") (pintype "bidirectional"))
    )
    (net (code "111") (name "OUT6") (class "Default")
      (node (ref "R20") (pin "2") (pinfunction "2_2") (pintype "passive"))
      (node (ref "R29") (pin "2") (pinfunction "2_2") (pintype "passive"))
      (node (ref "R38") (pin "2") (pinfunction "2_2") (pintype "passive"))
      (node (ref "R47") (pin "2") (pinfunction "2_2") (pintype "passive"))
      (node (ref "R56") (pin "2") (pinfunction "2_2") (pintype "passive"))
      (node (ref "R65") (pin "2") (pinfunction "2_2") (pintype "passive"))
      (node (ref "R74") (pin "2") (pinfunction "2_2") (pintype "passive"))
      (node (ref "R98") (pin "2") (pinfunction "2_2") (pintype "passive"))
      (node (ref "U$2") (pin "38") (pinfunction "PF5(ADC5/TMS)_38") (pintype "bidirectional"))
    )
    (net (code "112") (name "OUT7") (class "Default")
      (node (ref "R21") (pin "2") (pinfunction "2_2") (pintype "passive"))
      (node (ref "R30") (pin "2") (pinfunction "2_2") (pintype "passive"))
      (node (ref "R39") (pin "2") (pinfunction "2_2") (pintype "passive"))
      (node (ref "R48") (pin "2") (pinfunction "2_2") (pintype "passive"))
      (node (ref "R57") (pin "2") (pinfunction "2_2") (pintype "passive"))
      (node (ref "R66") (pin "2") (pinfunction "2_2") (pintype "passive"))
      (node (ref "R75") (pin "2") (pinfunction "2_2") (pintype "passive"))
      (node (ref "U$2") (pin "12") (pinfunction "PB7(OC0A/OC1C/RTS)_12") (pintype "bidirectional"))
    )
    (net (code "113") (name "OUT8") (class "Default")
      (node (ref "R22") (pin "2") (pinfunction "2_2") (pintype "passive"))
      (node (ref "R31") (pin "2") (pinfunction "2_2") (pintype "passive"))
      (node (ref "R40") (pin "2") (pinfunction "2_2") (pintype "passive"))
      (node (ref "R49") (pin "2") (pinfunction "2_2") (pintype "passive"))
      (node (ref "R58") (pin "2") (pinfunction "2_2") (pintype "passive"))
      (node (ref "R67") (pin "2") (pinfunction "2_2") (pintype "passive"))
      (node (ref "R76") (pin "2") (pinfunction "2_2") (pintype "passive"))
      (node (ref "U$2") (pin "32") (pinfunction "PC7(ICP3/CLK0/OC4A)_32") (pintype "bidirectional"))
    )
    (net (code "114") (name "OUT9") (class "Default")
      (node (ref "R23") (pin "2") (pinfunction "2_2") (pintype "passive"))
      (node (ref "R32") (pin "2") (pinfunction "2_2") (pintype "passive"))
      (node (ref "R41") (pin "2") (pinfunction "2_2") (pintype "passive"))
      (node (ref "R50") (pin "2") (pinfunction "2_2") (pintype "passive"))
      (node (ref "R59") (pin "2") (pinfunction "2_2") (pintype "passive"))
      (node (ref "R68") (pin "2") (pinfunction "2_2") (pintype "passive"))
      (node (ref "R77") (pin "2") (pinfunction "2_2") (pintype "passive"))
      (node (ref "U$2") (pin "31") (pinfunction "PC6(OC3A/~{OC4A})_31") (pintype "bidirectional"))
    )
    (net (code "115") (name "PWRSWITCH") (class "Default")
      (node (ref "S5") (pin "2") (pinfunction "2_2") (pintype "bidirectional"))
      (node (ref "U$166") (pin "1") (pinfunction "SHDN_1") (pintype "bidirectional"))
    )
    (net (code "116") (name "RESET1") (class "Default")
      (node (ref "C45") (pin "2") (pinfunction "2_2") (pintype "passive"))
      (node (ref "S2") (pin "3") (pinfunction "2_3") (pintype "passive"))
      (node (ref "U3") (pin "5") (pinfunction "~{RESET}_5") (pintype "input"))
    )
    (net (code "117") (name "RESET2") (class "Default")
      (node (ref "C43") (pin "2") (pinfunction "2_2") (pintype "passive"))
      (node (ref "S3") (pin "3") (pinfunction "2_3") (pintype "passive"))
      (node (ref "U1") (pin "5") (pinfunction "~{RESET}_5") (pintype "input"))
    )
    (net (code "118") (name "RESET3") (class "Default")
      (node (ref "C44") (pin "2") (pinfunction "2_2") (pintype "passive"))
      (node (ref "S4") (pin "3") (pinfunction "2_3") (pintype "passive"))
      (node (ref "U2") (pin "5") (pinfunction "~{RESET}_5") (pintype "input"))
    )
    (net (code "119") (name "RST") (class "Default")
      (node (ref "C46") (pin "2") (pinfunction "2_2") (pintype "passive"))
      (node (ref "S1") (pin "1") (pinfunction "1_1") (pintype "passive"))
      (node (ref "U$2") (pin "13") (pinfunction "/RESET_13") (pintype "bidirectional"))
      (node (ref "U$59") (pin "RST") (pinfunction "RST_RST") (pintype "bidirectional"))
    )
    (net (code "120") (name "SCK") (class "Default")
      (node (ref "U$2") (pin "9") (pinfunction "PB1(SCK)_9") (pintype "bidirectional"))
      (node (ref "U$59") (pin "SCK") (pinfunction "SCK_SCK") (pintype "bidirectional"))
    )
    (net (code "121") (name "STATUSLED1") (class "Default")
      (node (ref "R7") (pin "2") (pinfunction "2_2") (pintype "passive"))
      (node (ref "U3") (pin "21") (pinfunction "GPIO5_21") (pintype "bidirectional"))
    )
    (net (code "122") (name "STATUSLED2") (class "Default")
      (node (ref "R10") (pin "2") (pinfunction "2_2") (pintype "passive"))
      (node (ref "U1") (pin "21") (pinfunction "GPIO5_21") (pintype "bidirectional"))
    )
    (net (code "123") (name "STATUSLED3") (class "Default")
      (node (ref "R13") (pin "2") (pinfunction "2_2") (pintype "passive"))
      (node (ref "U2") (pin "21") (pinfunction "GPIO5_21") (pintype "bidirectional"))
    )
    (net (code "124") (name "TX1") (class "Default")
      (node (ref "U$2") (pin "21") (pinfunction "PD3(INT3/TXD1)_21") (pintype "bidirectional"))
      (node (ref "U3") (pin "13") (pinfunction "UART_RX_13") (pintype "input"))
    )
    (net (code "125") (name "TX2") (class "Default")
      (node (ref "U$2") (pin "25") (pinfunction "PD4(ICP1/ADC8)_25") (pintype "bidirectional"))
      (node (ref "U1") (pin "13") (pinfunction "UART_RX_13") (pintype "input"))
    )
    (net (code "126") (name "TX3") (class "Default")
      (node (ref "U$2") (pin "26") (pinfunction "PD6(T1/ADC9/~{OC4D})_26") (pintype "bidirectional"))
      (node (ref "U2") (pin "13") (pinfunction "UART_RX_13") (pintype "input"))
    )
    (net (code "127") (name "TXRXLED1") (class "Default")
      (node (ref "R8") (pin "2") (pinfunction "2_2") (pintype "passive"))
      (node (ref "U3") (pin "31") (pinfunction "GPIO8_31") (pintype "bidirectional"))
    )
    (net (code "128") (name "TXRXLED2") (class "Default")
      (node (ref "R11") (pin "2") (pinfunction "2_2") (pintype "passive"))
      (node (ref "U1") (pin "31") (pinfunction "GPIO8_31") (pintype "bidirectional"))
    )
    (net (code "129") (name "TXRXLED3") (class "Default")
      (node (ref "R14") (pin "2") (pinfunction "2_2") (pintype "passive"))
      (node (ref "U2") (pin "31") (pinfunction "GPIO8_31") (pintype "bidirectional"))
    )
    (net (code "130") (name "VBUS") (class "Default")
      (node (ref "C42") (pin "1") (pinfunction "1_1") (pintype "passive"))
      (node (ref "U$2") (pin "7") (pinfunction "VBUS_7") (pintype "bidirectional"))
      (node (ref "X2") (pin "1") (pinfunction "1_1") (pintype "passive"))
    )
    (net (code "131") (name "VIN") (class "Default")
      (node (ref "BT1") (pin "PWR@1") (pinfunction "+_PWR@1") (pintype "power_in"))
      (node (ref "C47") (pin "1") (pinfunction "1_1") (pintype "passive"))
      (node (ref "S5") (pin "1") (pinfunction "1_1") (pintype "bidirectional"))
      (node (ref "U$166") (pin "2") (pinfunction "IN_2") (pintype "bidirectional"))
    )
    (net (code "132") (name "XTAL1") (class "Default")
      (node (ref "C3") (pin "2") (pinfunction "2_2") (pintype "passive"))
      (node (ref "U$2") (pin "17") (pinfunction "XTAL1_17") (pintype "bidirectional"))
      (node (ref "Y2") (pin "2") (pinfunction "2_2") (pintype "passive"))
    )
    (net (code "133") (name "XTAL2") (class "Default")
      (node (ref "C4") (pin "2") (pinfunction "2_2") (pintype "passive"))
      (node (ref "U$2") (pin "16") (pinfunction "XTAL2_16") (pintype "bidirectional"))
      (node (ref "Y2") (pin "1") (pinfunction "1_1") (pintype "passive"))
    )
    (net (code "134") (name "unconnected-(U$2-PD2(INT2{slash}RXD1)-Pad20)") (class "Default")
      (node (ref "U$2") (pin "20") (pinfunction "PD2(INT2/RXD1)_20") (pintype "bidirectional"))
    )
    (net (code "135") (name "unconnected-(U$2-PE2(~{HWB})-Pad33)") (class "Default")
      (node (ref "U$2") (pin "33") (pinfunction "PE2(~{HWB})_33") (pintype "bidirectional"))
    )
    (net (code "136") (name "unconnected-(U$2-PF7(ADC7(TDI)-Pad36)") (class "Default")
      (node (ref "U$2") (pin "36") (pinfunction "PF7(ADC7(TDI)_36") (pintype "bidirectional"))
    )
    (net (code "137") (name "unconnected-(U1-AIO0-Pad30)") (class "Default")
      (node (ref "U1") (pin "30") (pinfunction "AIO0_30") (pintype "bidirectional"))
    )
    (net (code "138") (name "unconnected-(U1-AIO1-Pad35)") (class "Default")
      (node (ref "U1") (pin "35") (pinfunction "AIO1_35") (pintype "bidirectional"))
    )
    (net (code "139") (name "unconnected-(U1-GPIO3-Pad20)") (class "Default")
      (node (ref "U1") (pin "20") (pinfunction "GPIO3_20") (pintype "bidirectional"))
    )
    (net (code "140") (name "unconnected-(U1-GPIO6-Pad3)") (class "Default")
      (node (ref "U1") (pin "3") (pinfunction "GPIO6_3") (pintype "bidirectional"))
    )
    (net (code "141") (name "unconnected-(U1-GPIO7-Pad4)") (class "Default")
      (node (ref "U1") (pin "4") (pinfunction "GPIO7_4") (pintype "bidirectional"))
    )
    (net (code "142") (name "unconnected-(U1-GPIO9-Pad32)") (class "Default")
      (node (ref "U1") (pin "32") (pinfunction "GPIO9_32") (pintype "bidirectional"))
    )
    (net (code "143") (name "unconnected-(U1-GPIO10-Pad33)") (class "Default")
      (node (ref "U1") (pin "33") (pinfunction "GPIO10_33") (pintype "bidirectional"))
    )
    (net (code "144") (name "unconnected-(U1-GPIO11-Pad34)") (class "Default")
      (node (ref "U1") (pin "34") (pinfunction "GPIO11_34") (pintype "bidirectional"))
    )
    (net (code "145") (name "unconnected-(U1-PCM_CLK-Pad7)") (class "Default")
      (node (ref "U1") (pin "7") (pinfunction "PCM_CLK_7") (pintype "bidirectional"))
    )
    (net (code "146") (name "unconnected-(U1-PCM_IN-Pad9)") (class "Default")
      (node (ref "U1") (pin "9") (pinfunction "PCM_IN_9") (pintype "input"))
    )
    (net (code "147") (name "unconnected-(U1-PCM_OUT-Pad10)") (class "Default")
      (node (ref "U1") (pin "10") (pinfunction "PCM_OUT_10") (pintype "output"))
    )
    (net (code "148") (name "unconnected-(U1-PCM_SYNC-Pad8)") (class "Default")
      (node (ref "U1") (pin "8") (pinfunction "PCM_SYNC_8") (pintype "bidirectional"))
    )
    (net (code "149") (name "unconnected-(U1-SPI_CLK-Pad6)") (class "Default")
      (node (ref "U1") (pin "6") (pinfunction "SPI_CLK_6") (pintype "input"))
    )
    (net (code "150") (name "unconnected-(U1-SPI_CSB-Pad23)") (class "Default")
      (node (ref "U1") (pin "23") (pinfunction "SPI_CSB_23") (pintype "input"))
    )
    (net (code "151") (name "unconnected-(U1-SPI_MISO-Pad24)") (class "Default")
      (node (ref "U1") (pin "24") (pinfunction "SPI_MISO_24") (pintype "output"))
    )
    (net (code "152") (name "unconnected-(U1-SPI_MOSI-Pad2)") (class "Default")
      (node (ref "U1") (pin "2") (pinfunction "SPI_MOSI_2") (pintype "input"))
    )
    (net (code "153") (name "unconnected-(U1-UART_RTS-Pad15)") (class "Default")
      (node (ref "U1") (pin "15") (pinfunction "UART_RTS_15") (pintype "output"))
    )
    (net (code "154") (name "unconnected-(U1-UART_TX-Pad14)") (class "Default")
      (node (ref "U1") (pin "14") (pinfunction "UART_TX_14") (pintype "output"))
    )
    (net (code "155") (name "unconnected-(U1-USB_D+-Pad17)") (class "Default")
      (node (ref "U1") (pin "17") (pinfunction "USB_D+_17") (pintype "bidirectional"))
    )
    (net (code "156") (name "unconnected-(U1-USB_D--Pad18)") (class "Default")
      (node (ref "U1") (pin "18") (pinfunction "USB_D-_18") (pintype "bidirectional"))
    )
    (net (code "157") (name "unconnected-(U2-AIO0-Pad30)") (class "Default")
      (node (ref "U2") (pin "30") (pinfunction "AIO0_30") (pintype "bidirectional"))
    )
    (net (code "158") (name "unconnected-(U2-AIO1-Pad35)") (class "Default")
      (node (ref "U2") (pin "35") (pinfunction "AIO1_35") (pintype "bidirectional"))
    )
    (net (code "159") (name "unconnected-(U2-GPIO3-Pad20)") (class "Default")
      (node (ref "U2") (pin "20") (pinfunction "GPIO3_20") (pintype "bidirectional"))
    )
    (net (code "160") (name "unconnected-(U2-GPIO6-Pad3)") (class "Default")
      (node (ref "U2") (pin "3") (pinfunction "GPIO6_3") (pintype "bidirectional"))
    )
    (net (code "161") (name "unconnected-(U2-GPIO7-Pad4)") (class "Default")
      (node (ref "U2") (pin "4") (pinfunction "GPIO7_4") (pintype "bidirectional"))
    )
    (net (code "162") (name "unconnected-(U2-GPIO9-Pad32)") (class "Default")
      (node (ref "U2") (pin "32") (pinfunction "GPIO9_32") (pintype "bidirectional"))
    )
    (net (code "163") (name "unconnected-(U2-GPIO10-Pad33)") (class "Default")
      (node (ref "U2") (pin "33") (pinfunction "GPIO10_33") (pintype "bidirectional"))
    )
    (net (code "164") (name "unconnected-(U2-GPIO11-Pad34)") (class "Default")
      (node (ref "U2") (pin "34") (pinfunction "GPIO11_34") (pintype "bidirectional"))
    )
    (net (code "165") (name "unconnected-(U2-PCM_CLK-Pad7)") (class "Default")
      (node (ref "U2") (pin "7") (pinfunction "PCM_CLK_7") (pintype "bidirectional"))
    )
    (net (code "166") (name "unconnected-(U2-PCM_IN-Pad9)") (class "Default")
      (node (ref "U2") (pin "9") (pinfunction "PCM_IN_9") (pintype "input"))
    )
    (net (code "167") (name "unconnected-(U2-PCM_OUT-Pad10)") (class "Default")
      (node (ref "U2") (pin "10") (pinfunction "PCM_OUT_10") (pintype "output"))
    )
    (net (code "168") (name "unconnected-(U2-PCM_SYNC-Pad8)") (class "Default")
      (node (ref "U2") (pin "8") (pinfunction "PCM_SYNC_8") (pintype "bidirectional"))
    )
    (net (code "169") (name "unconnected-(U2-SPI_CLK-Pad6)") (class "Default")
      (node (ref "U2") (pin "6") (pinfunction "SPI_CLK_6") (pintype "input"))
    )
    (net (code "170") (name "unconnected-(U2-SPI_CSB-Pad23)") (class "Default")
      (node (ref "U2") (pin "23") (pinfunction "SPI_CSB_23") (pintype "input"))
    )
    (net (code "171") (name "unconnected-(U2-SPI_MISO-Pad24)") (class "Default")
      (node (ref "U2") (pin "24") (pinfunction "SPI_MISO_24") (pintype "output"))
    )
    (net (code "172") (name "unconnected-(U2-SPI_MOSI-Pad2)") (class "Default")
      (node (ref "U2") (pin "2") (pinfunction "SPI_MOSI_2") (pintype "input"))
    )
    (net (code "173") (name "unconnected-(U2-UART_RTS-Pad15)") (class "Default")
      (node (ref "U2") (pin "15") (pinfunction "UART_RTS_15") (pintype "output"))
    )
    (net (code "174") (name "unconnected-(U2-UART_TX-Pad14)") (class "Default")
      (node (ref "U2") (pin "14") (pinfunction "UART_TX_14") (pintype "output"))
    )
    (net (code "175") (name "unconnected-(U2-USB_D+-Pad17)") (class "Default")
      (node (ref "U2") (pin "17") (pinfunction "USB_D+_17") (pintype "bidirectional"))
    )
    (net (code "176") (name "unconnected-(U2-USB_D--Pad18)") (class "Default")
      (node (ref "U2") (pin "18") (pinfunction "USB_D-_18") (pintype "bidirectional"))
    )
    (net (code "177") (name "unconnected-(U3-AIO0-Pad30)") (class "Default")
      (node (ref "U3") (pin "30") (pinfunction "AIO0_30") (pintype "bidirectional"))
    )
    (net (code "178") (name "unconnected-(U3-AIO1-Pad35)") (class "Default")
      (node (ref "U3") (pin "35") (pinfunction "AIO1_35") (pintype "bidirectional"))
    )
    (net (code "179") (name "unconnected-(U3-GPIO3-Pad20)") (class "Default")
      (node (ref "U3") (pin "20") (pinfunction "GPIO3_20") (pintype "bidirectional"))
    )
    (net (code "180") (name "unconnected-(U3-GPIO6-Pad3)") (class "Default")
      (node (ref "U3") (pin "3") (pinfunction "GPIO6_3") (pintype "bidirectional"))
    )
    (net (code "181") (name "unconnected-(U3-GPIO7-Pad4)") (class "Default")
      (node (ref "U3") (pin "4") (pinfunction "GPIO7_4") (pintype "bidirectional"))
    )
    (net (code "182") (name "unconnected-(U3-GPIO9-Pad32)") (class "Default")
      (node (ref "U3") (pin "32") (pinfunction "GPIO9_32") (pintype "bidirectional"))
    )
    (net (code "183") (name "unconnected-(U3-GPIO10-Pad33)") (class "Default")
      (node (ref "U3") (pin "33") (pinfunction "GPIO10_33") (pintype "bidirectional"))
    )
    (net (code "184") (name "unconnected-(U3-GPIO11-Pad34)") (class "Default")
      (node (ref "U3") (pin "34") (pinfunction "GPIO11_34") (pintype "bidirectional"))
    )
    (net (code "185") (name "unconnected-(U3-PCM_CLK-Pad7)") (class "Default")
      (node (ref "U3") (pin "7") (pinfunction "PCM_CLK_7") (pintype "bidirectional"))
    )
    (net (code "186") (name "unconnected-(U3-PCM_IN-Pad9)") (class "Default")
      (node (ref "U3") (pin "9") (pinfunction "PCM_IN_9") (pintype "input"))
    )
    (net (code "187") (name "unconnected-(U3-PCM_OUT-Pad10)") (class "Default")
      (node (ref "U3") (pin "10") (pinfunction "PCM_OUT_10") (pintype "output"))
    )
    (net (code "188") (name "unconnected-(U3-PCM_SYNC-Pad8)") (class "Default")
      (node (ref "U3") (pin "8") (pinfunction "PCM_SYNC_8") (pintype "bidirectional"))
    )
    (net (code "189") (name "unconnected-(U3-SPI_CLK-Pad6)") (class "Default")
      (node (ref "U3") (pin "6") (pinfunction "SPI_CLK_6") (pintype "input"))
    )
    (net (code "190") (name "unconnected-(U3-SPI_CSB-Pad23)") (class "Default")
      (node (ref "U3") (pin "23") (pinfunction "SPI_CSB_23") (pintype "input"))
    )
    (net (code "191") (name "unconnected-(U3-SPI_MISO-Pad24)") (class "Default")
      (node (ref "U3") (pin "24") (pinfunction "SPI_MISO_24") (pintype "output"))
    )
    (net (code "192") (name "unconnected-(U3-SPI_MOSI-Pad2)") (class "Default")
      (node (ref "U3") (pin "2") (pinfunction "SPI_MOSI_2") (pintype "input"))
    )
    (net (code "193") (name "unconnected-(U3-UART_RTS-Pad15)") (class "Default")
      (node (ref "U3") (pin "15") (pinfunction "UART_RTS_15") (pintype "output"))
    )
    (net (code "194") (name "unconnected-(U3-UART_TX-Pad14)") (class "Default")
      (node (ref "U3") (pin "14") (pinfunction "UART_TX_14") (pintype "output"))
    )
    (net (code "195") (name "unconnected-(U3-USB_D+-Pad17)") (class "Default")
      (node (ref "U3") (pin "17") (pinfunction "USB_D+_17") (pintype "bidirectional"))
    )
    (net (code "196") (name "unconnected-(U3-USB_D--Pad18)") (class "Default")
      (node (ref "U3") (pin "18") (pinfunction "USB_D-_18") (pintype "bidirectional"))
    )
    (net (code "197") (name "unconnected-(X2-Pad4)") (class "Default")
      (node (ref "X2") (pin "4") (pinfunction "4_4") (pintype "passive"))
    )
  )
)
